# Sheet1.net
KiCad netlist of a schematic drawn in Altium Designer
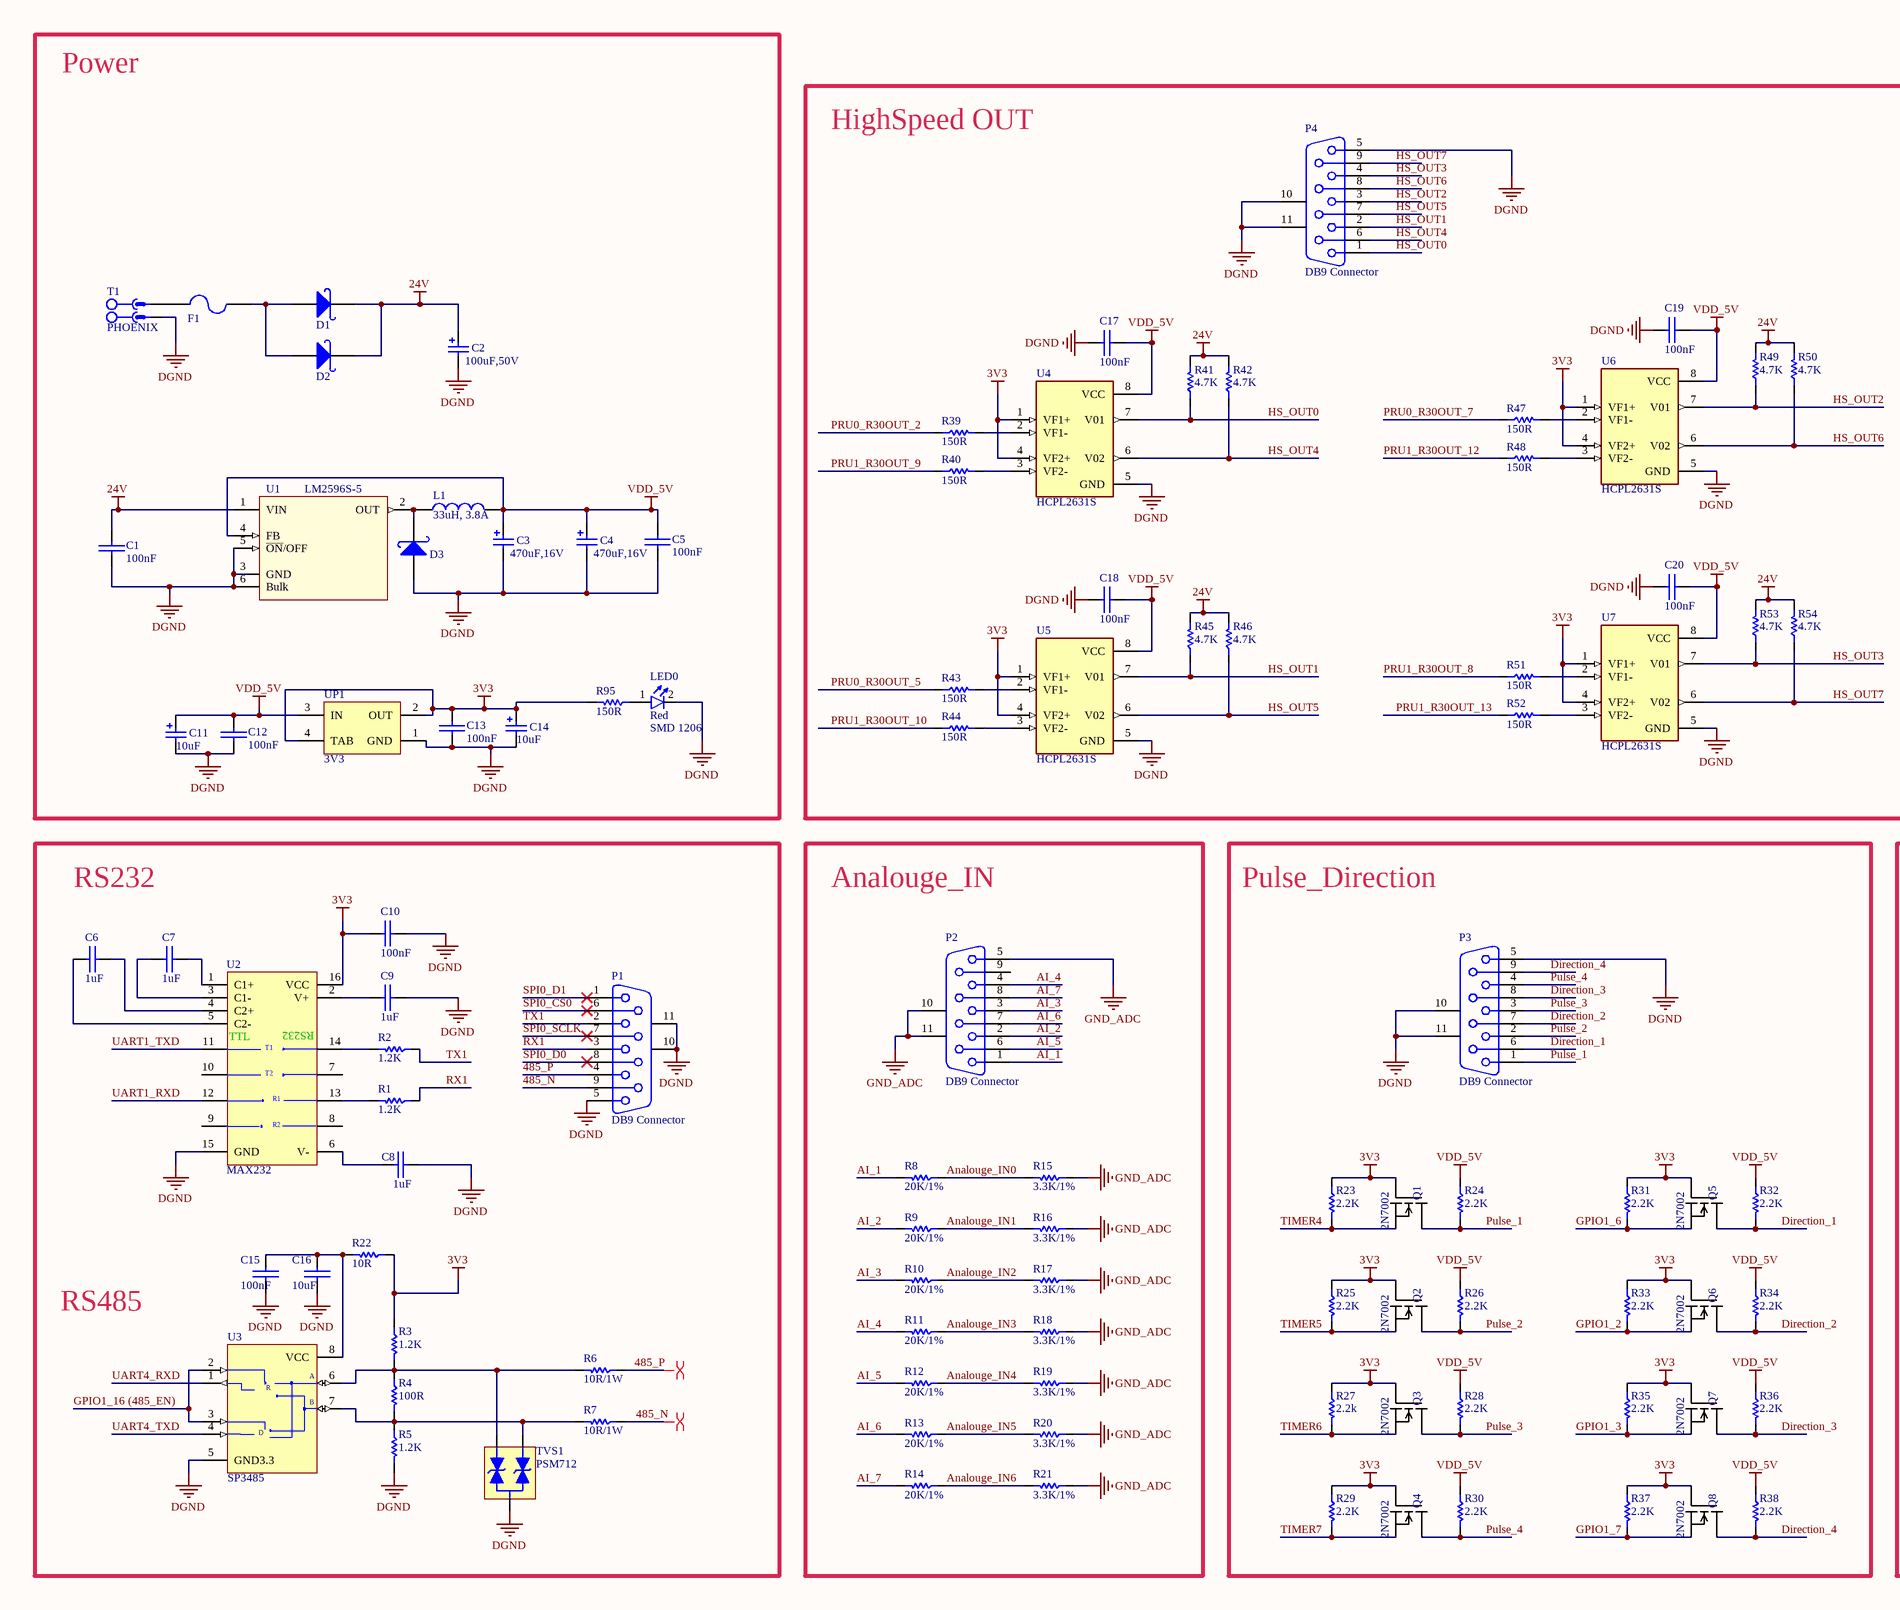
[diagram p0: Sheet1.SchDoc, left]
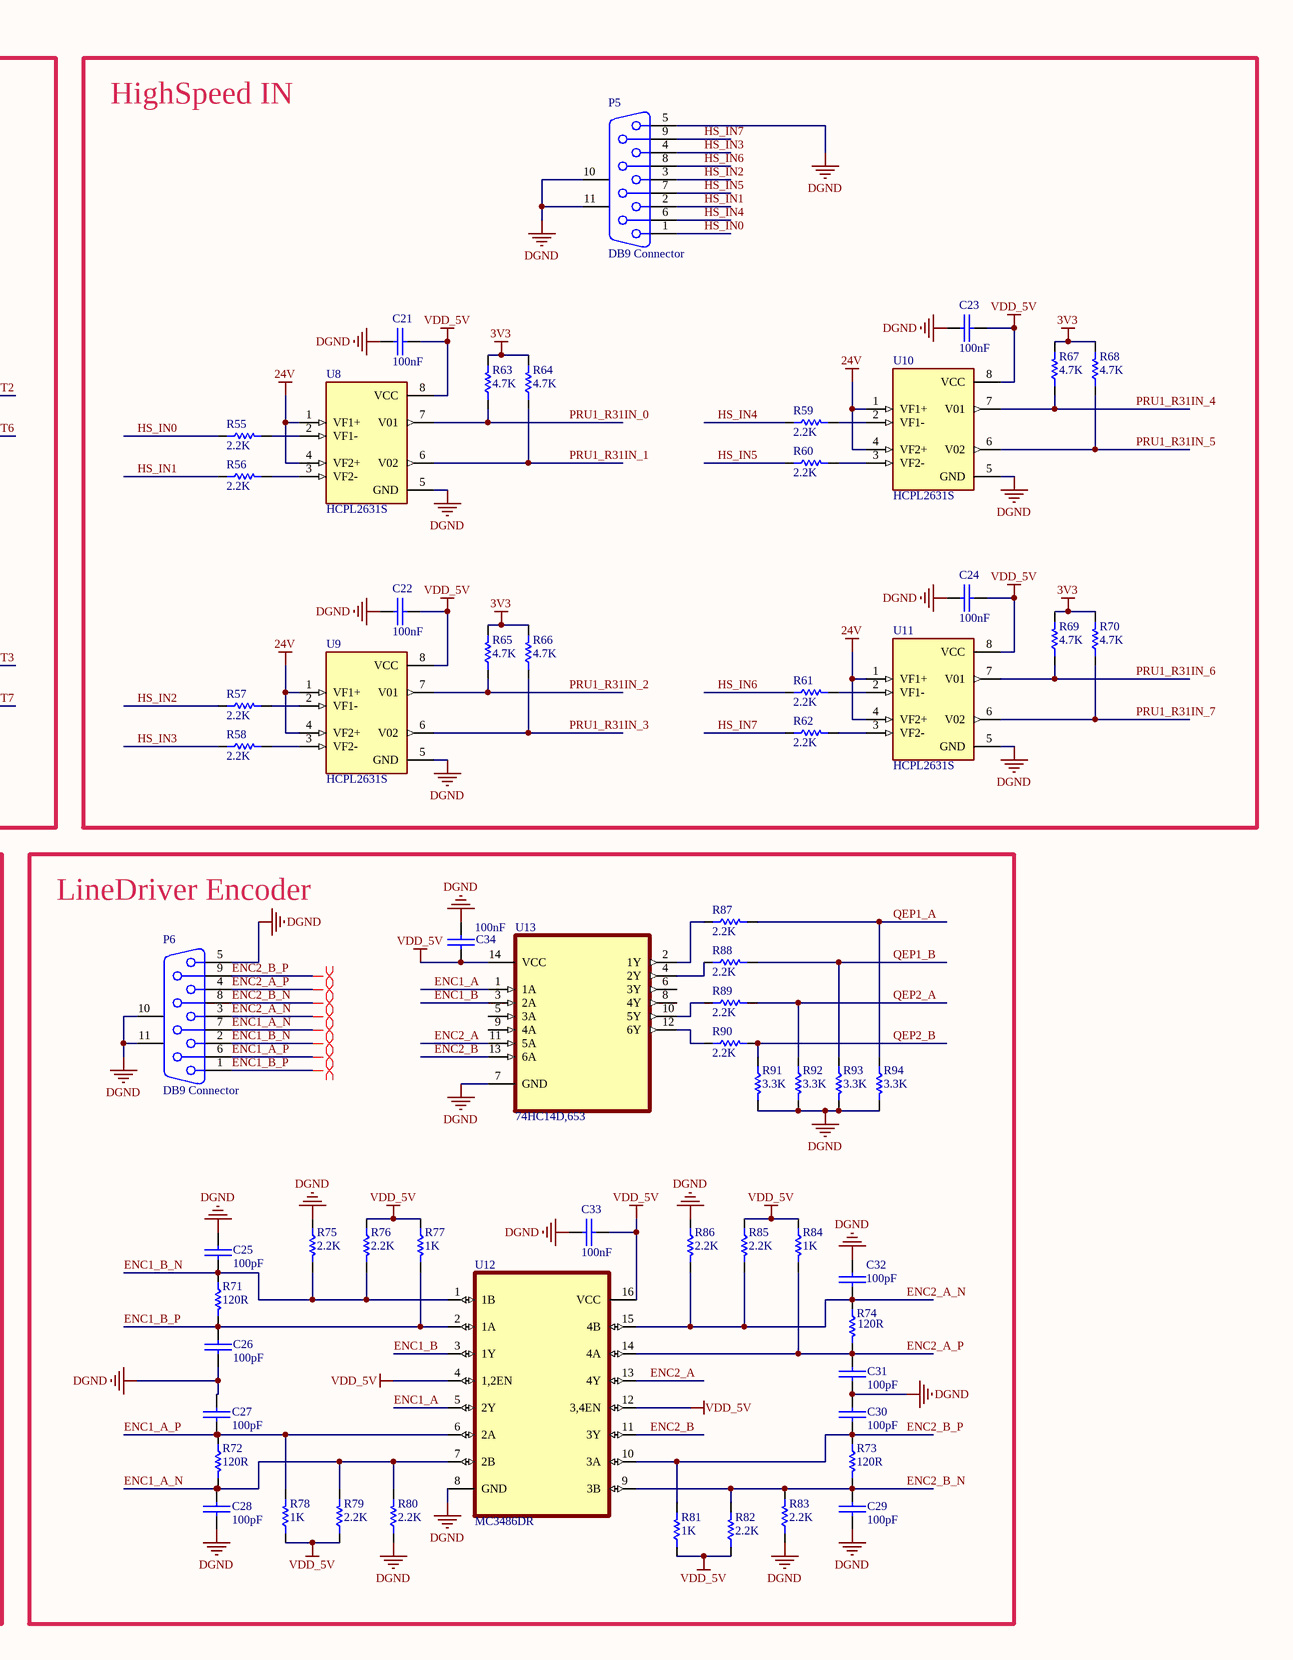
[diagram p1: Sheet1.SchDoc, right]

(export (version "E")
  (design (tool "Eeschema 10.0.6"))
  (components
    (comp (ref "C1")
      (value "100nF")
      (footprint "SMD_CAP_0805")
      (description "Bipolar Capacitor")
      (fields (field (name "VOLTAGE") "100V") (field (name "DESIGNER") "Saeid Jorablo"))
      (libsource (lib "My_Library") (part "Cap-Bipolar"))
    )
    (comp (ref "C2")
      (value "100uF,50V")
      (footprint "WCAP-AS5H_8x10.5")
      (description "WCAP-AS5H SMT Aluminum Electrolytic Capacitors, D8mm x L10.5mm, 47uF, +/-20%, 50VDC")
      (fields (field (name "PART NUMBER") "865230653012") (field (name "PUBLISHER") "Wurth Elektronik"))
      (libsource (lib "Altium_WCAP-AS5H (rev19a)") (part "865230653012"))
    )
    (comp (ref "C3")
      (value "470uF,16V")
      (footprint "WCAP-AS5H_8x10.5")
      (description "WCAP-AS5H SMT Aluminum Electrolytic Capacitors, D8mm x L10.5mm, 47uF, +/-20%, 50VDC")
      (fields (field (name "PART NUMBER") "865230653012") (field (name "PUBLISHER") "Wurth Elektronik"))
      (libsource (lib "Altium_WCAP-AS5H (rev19a)") (part "865230653012"))
    )
    (comp (ref "C4")
      (value "470uF,16V")
      (footprint "WCAP-AS5H_8x10.5")
      (description "WCAP-AS5H SMT Aluminum Electrolytic Capacitors, D8mm x L10.5mm, 47uF, +/-20%, 50VDC")
      (fields (field (name "PART NUMBER") "865230653012") (field (name "PUBLISHER") "Wurth Elektronik"))
      (libsource (lib "Altium_WCAP-AS5H (rev19a)") (part "865230653012"))
    )
    (comp (ref "C5")
      (value "100nF")
      (footprint "SMD_CAP_0805")
      (description "Bipolar Capacitor")
      (fields (field (name "VOLTAGE") "100V") (field (name "DESIGNER") "Saeid Jorablo"))
      (libsource (lib "My_Library") (part "Cap-Bipolar"))
    )
    (comp (ref "C6")
      (value "1uF")
      (footprint "SMD_CAP_0805")
      (description "Bipolar Capacitor")
      (fields (field (name "VOLTAGE") "100V") (field (name "DESIGNER") "Saeid Jorablo"))
      (libsource (lib "My_Library") (part "Cap-Bipolar"))
    )
    (comp (ref "C7")
      (value "1uF")
      (footprint "SMD_CAP_0805")
      (description "Bipolar Capacitor")
      (fields (field (name "VOLTAGE") "100V") (field (name "DESIGNER") "Saeid Jorablo"))
      (libsource (lib "My_Library") (part "Cap-Bipolar"))
    )
    (comp (ref "C8")
      (value "1uF")
      (footprint "SMD_CAP_0805")
      (description "Bipolar Capacitor")
      (fields (field (name "VOLTAGE") "100V") (field (name "DESIGNER") "Saeid Jorablo"))
      (libsource (lib "My_Library") (part "Cap-Bipolar"))
    )
    (comp (ref "C9")
      (value "1uF")
      (footprint "SMD_CAP_0805")
      (description "Bipolar Capacitor")
      (fields (field (name "VOLTAGE") "100V") (field (name "DESIGNER") "Saeid Jorablo"))
      (libsource (lib "My_Library") (part "Cap-Bipolar"))
    )
    (comp (ref "C10")
      (value "100nF")
      (footprint "SMD_CAP_0805")
      (description "Bipolar Capacitor")
      (fields (field (name "VOLTAGE") "100V") (field (name "DESIGNER") "Saeid Jorablo"))
      (libsource (lib "My_Library") (part "Cap-Bipolar"))
    )
    (comp (ref "C11")
      (value "10uF")
      (footprint "WCAP-AS5H_4x5.5")
      (description "WCAP-AS5H SMT Aluminum Electrolytic Capacitors, D4mm x L5.5mm, 22uF, +/-20%, 6.3VDC")
      (fields (field (name "PART NUMBER") "865230140001") (field (name "PUBLISHER") "Wurth Elektronik"))
      (libsource (lib "Altium_WCAP-AS5H (rev19a)") (part "865230140001"))
    )
    (comp (ref "C12")
      (value "100nF")
      (footprint "SMD_CAP_0805")
      (description "Bipolar Capacitor")
      (fields (field (name "VOLTAGE") "100V") (field (name "DESIGNER") "Saeid Jorablo"))
      (libsource (lib "My_Library") (part "Cap-Bipolar"))
    )
    (comp (ref "C13")
      (value "100nF")
      (footprint "SMD_CAP_0805")
      (description "Bipolar Capacitor")
      (fields (field (name "VOLTAGE") "100V") (field (name "DESIGNER") "Saeid Jorablo"))
      (libsource (lib "My_Library") (part "Cap-Bipolar"))
    )
    (comp (ref "C14")
      (value "10uF")
      (footprint "WCAP-AS5H_4x5.5")
      (description "WCAP-AS5H SMT Aluminum Electrolytic Capacitors, D4mm x L5.5mm, 22uF, +/-20%, 6.3VDC")
      (fields (field (name "PART NUMBER") "865230140001") (field (name "PUBLISHER") "Wurth Elektronik"))
      (libsource (lib "Altium_WCAP-AS5H (rev19a)") (part "865230140001"))
    )
    (comp (ref "C15")
      (value "100nF")
      (footprint "SMD_CAP_0805")
      (description "Bipolar Capacitor")
      (fields (field (name "VOLTAGE") "100V") (field (name "DESIGNER") "Saeid Jorablo"))
      (libsource (lib "My_Library") (part "Cap-Bipolar"))
    )
    (comp (ref "C16")
      (value "10uF")
      (footprint "SMD_CAP_0805")
      (description "Bipolar Capacitor")
      (fields (field (name "VOLTAGE") "100V") (field (name "DESIGNER") "Saeid Jorablo"))
      (libsource (lib "My_Library") (part "Cap-Bipolar"))
    )
    (comp (ref "C17")
      (value "100nF")
      (footprint "SMD_CAP_0805")
      (description "Bipolar Capacitor")
      (fields (field (name "VOLTAGE") "100V") (field (name "DESIGNER") "Saeid Jorablo"))
      (libsource (lib "My_Library") (part "Cap-Bipolar"))
    )
    (comp (ref "C18")
      (value "100nF")
      (footprint "SMD_CAP_0805")
      (description "Bipolar Capacitor")
      (fields (field (name "VOLTAGE") "100V") (field (name "DESIGNER") "Saeid Jorablo"))
      (libsource (lib "My_Library") (part "Cap-Bipolar"))
    )
    (comp (ref "C19")
      (value "100nF")
      (footprint "SMD_CAP_0805")
      (description "Bipolar Capacitor")
      (fields (field (name "VOLTAGE") "100V") (field (name "DESIGNER") "Saeid Jorablo"))
      (libsource (lib "My_Library") (part "Cap-Bipolar"))
    )
    (comp (ref "C20")
      (value "100nF")
      (footprint "SMD_CAP_0805")
      (description "Bipolar Capacitor")
      (fields (field (name "VOLTAGE") "100V") (field (name "DESIGNER") "Saeid Jorablo"))
      (libsource (lib "My_Library") (part "Cap-Bipolar"))
    )
    (comp (ref "C21")
      (value "100nF")
      (footprint "SMD_CAP_0805")
      (description "Bipolar Capacitor")
      (fields (field (name "VOLTAGE") "100V") (field (name "DESIGNER") "Saeid Jorablo"))
      (libsource (lib "My_Library") (part "Cap-Bipolar"))
    )
    (comp (ref "C22")
      (value "100nF")
      (footprint "SMD_CAP_0805")
      (description "Bipolar Capacitor")
      (fields (field (name "VOLTAGE") "100V") (field (name "DESIGNER") "Saeid Jorablo"))
      (libsource (lib "My_Library") (part "Cap-Bipolar"))
    )
    (comp (ref "C23")
      (value "100nF")
      (footprint "SMD_CAP_0805")
      (description "Bipolar Capacitor")
      (fields (field (name "VOLTAGE") "100V") (field (name "DESIGNER") "Saeid Jorablo"))
      (libsource (lib "My_Library") (part "Cap-Bipolar"))
    )
    (comp (ref "C24")
      (value "100nF")
      (footprint "SMD_CAP_0805")
      (description "Bipolar Capacitor")
      (fields (field (name "VOLTAGE") "100V") (field (name "DESIGNER") "Saeid Jorablo"))
      (libsource (lib "My_Library") (part "Cap-Bipolar"))
    )
    (comp (ref "C25")
      (value "100pF")
      (footprint "SMD_CAP_0805")
      (description "Bipolar Capacitor")
      (fields (field (name "VOLTAGE") "100V") (field (name "DESIGNER") "Saeid Jorablo"))
      (libsource (lib "My_Library") (part "Cap-Bipolar"))
    )
    (comp (ref "C26")
      (value "100pF")
      (footprint "SMD_CAP_0805")
      (description "Bipolar Capacitor")
      (fields (field (name "VOLTAGE") "100V") (field (name "DESIGNER") "Saeid Jorablo"))
      (libsource (lib "My_Library") (part "Cap-Bipolar"))
    )
    (comp (ref "C27")
      (value "100pF")
      (footprint "SMD_CAP_0805")
      (description "Bipolar Capacitor")
      (fields (field (name "VOLTAGE") "100V") (field (name "DESIGNER") "Saeid Jorablo"))
      (libsource (lib "My_Library") (part "Cap-Bipolar"))
    )
    (comp (ref "C28")
      (value "100pF")
      (footprint "SMD_CAP_0805")
      (description "Bipolar Capacitor")
      (fields (field (name "VOLTAGE") "100V") (field (name "DESIGNER") "Saeid Jorablo"))
      (libsource (lib "My_Library") (part "Cap-Bipolar"))
    )
    (comp (ref "C29")
      (value "100pF")
      (footprint "SMD_CAP_0805")
      (description "Bipolar Capacitor")
      (fields (field (name "VOLTAGE") "100V") (field (name "DESIGNER") "Saeid Jorablo"))
      (libsource (lib "My_Library") (part "Cap-Bipolar"))
    )
    (comp (ref "C30")
      (value "100pF")
      (footprint "SMD_CAP_0805")
      (description "Bipolar Capacitor")
      (fields (field (name "VOLTAGE") "100V") (field (name "DESIGNER") "Saeid Jorablo"))
      (libsource (lib "My_Library") (part "Cap-Bipolar"))
    )
    (comp (ref "C31")
      (value "100pF")
      (footprint "SMD_CAP_0805")
      (description "Bipolar Capacitor")
      (fields (field (name "VOLTAGE") "100V") (field (name "DESIGNER") "Saeid Jorablo"))
      (libsource (lib "My_Library") (part "Cap-Bipolar"))
    )
    (comp (ref "C32")
      (value "100pF")
      (footprint "SMD_CAP_0805")
      (description "Bipolar Capacitor")
      (fields (field (name "VOLTAGE") "100V") (field (name "DESIGNER") "Saeid Jorablo"))
      (libsource (lib "My_Library") (part "Cap-Bipolar"))
    )
    (comp (ref "C33")
      (value "100nF")
      (footprint "SMD_CAP_0805")
      (description "Bipolar Capacitor")
      (fields (field (name "VOLTAGE") "100V") (field (name "DESIGNER") "Saeid Jorablo"))
      (libsource (lib "My_Library") (part "Cap-Bipolar"))
    )
    (comp (ref "C34")
      (value "100nF")
      (footprint "SMD_CAP_0805")
      (description "Bipolar Capacitor")
      (fields (field (name "VOLTAGE") "100V") (field (name "DESIGNER") "Saeid Jorablo"))
      (libsource (lib "My_Library") (part "Cap-Bipolar"))
    )
    (comp (ref "D1")
      (value "1n5822")
      (footprint "Diode 1N4007 SMD")
      (description "Schottky Rectifiers")
      (fields
        (field (name "MANUFACTURER") "ON Semiconductor/Fairchild")
        (field (name "DESIGNER") "Abbas Basereh")
      )
      (libsource (lib "Altium") (part "1N5822 SMD"))
    )
    (comp (ref "D2")
      (value "1n5822")
      (footprint "Diode 1N4007 SMD")
      (description "Schottky Rectifiers")
      (fields
        (field (name "MANUFACTURER") "ON Semiconductor/Fairchild")
        (field (name "DESIGNER") "Abbas Basereh")
      )
      (libsource (lib "Altium") (part "1N5822 SMD"))
    )
    (comp (ref "D3")
      (value "1n5822")
      (footprint "Diode 1N4007 SMD")
      (description "Schottky Rectifiers")
      (fields
        (field (name "MANUFACTURER") "ON Semiconductor/Fairchild")
        (field (name "DESIGNER") "Abbas Basereh")
      )
      (libsource (lib "Altium") (part "1N5822 SMD"))
    )
    (comp (ref "F1")
      (value "F=1.0 A")
      (footprint "1206 FUSE")
      (description "SMD Fuses 1206")
      (fields (field (name "DESIGNER") "Abbas Basereh"))
      (libsource (lib "Altium") (part "Fuse SMD1206"))
    )
    (comp (ref "L1")
      (value "33uH, 3.8A")
      (footprint "WE-PD_1210")
      (description "WE-PD SMT Power Inductor, size 1210, 47uH, 3.8A")
      (fields (field (name "PART NUMBER") "7447709470") (field (name "PUBLISHER") "Wurth Elektronik"))
      (libsource (lib "ALTIUM-WE-PD-rev19b") (part "7447709470"))
    )
    (comp (ref "LED0")
      (value "Red")
      (footprint "LED-3mm")
      (description "LED")
      (fields
        (field (name "COLOR") "Red")
        (field (name "SIZE") "SMD 1206")
        (field (name "DESIGNER") "Saeid Jorablo")
      )
      (libsource (lib "My_Library") (part "LED"))
    )
    (comp (ref "P1")
      (value "DB9 Connector")
      (footprint "DB9 Female")
      (description "Receptacle Assembly, 9 Position, Right Angle")
      (fields (field (name "PUBLISHER") "Altium Limited"))
      (libsource (lib "My_Library") (part "DB9 Connector"))
    )
    (comp (ref "P2")
      (value "DB9 Connector")
      (footprint "DB9 Female")
      (description "Receptacle Assembly, 9 Position, Right Angle")
      (fields (field (name "PUBLISHER") "Altium Limited"))
      (libsource (lib "My_Library") (part "DB9 Connector"))
    )
    (comp (ref "P3")
      (value "DB9 Connector")
      (footprint "DB9 Female")
      (description "Receptacle Assembly, 9 Position, Right Angle")
      (fields (field (name "PUBLISHER") "Altium Limited"))
      (libsource (lib "My_Library") (part "DB9 Connector"))
    )
    (comp (ref "P4")
      (value "DB9 Connector")
      (footprint "DB9 Female")
      (description "Receptacle Assembly, 9 Position, Right Angle")
      (fields (field (name "PUBLISHER") "Altium Limited"))
      (libsource (lib "My_Library") (part "DB9 Connector"))
    )
    (comp (ref "P5")
      (value "DB9 Connector")
      (footprint "DB9 Female")
      (description "Receptacle Assembly, 9 Position, Right Angle")
      (fields (field (name "PUBLISHER") "Altium Limited"))
      (libsource (lib "My_Library") (part "DB9 Connector"))
    )
    (comp (ref "P6")
      (value "DB9 Connector")
      (footprint "DB9 Female")
      (description "Receptacle Assembly, 9 Position, Right Angle")
      (fields (field (name "PUBLISHER") "Altium Limited"))
      (libsource (lib "My_Library") (part "DB9 Connector"))
    )
    (comp (ref "Q1")
      (value "2N7002")
      (footprint "*SOT23")
      (description "Transistor NPN Mos 2N7002 SILICONIX miliampere=100 V=60 SOt23")
      (fields (field (name "MF") "STMicroelectronics"))
      (libsource (lib "2N7002") (part "2N7002"))
    )
    (comp (ref "Q2")
      (value "2N7002")
      (footprint "*SOT23")
      (description "Transistor NPN Mos 2N7002 SILICONIX miliampere=100 V=60 SOt23")
      (fields (field (name "MF") "STMicroelectronics"))
      (libsource (lib "2N7002") (part "2N7002"))
    )
    (comp (ref "Q3")
      (value "2N7002")
      (footprint "*SOT23")
      (description "Transistor NPN Mos 2N7002 SILICONIX miliampere=100 V=60 SOt23")
      (fields (field (name "MF") "STMicroelectronics"))
      (libsource (lib "2N7002") (part "2N7002"))
    )
    (comp (ref "Q4")
      (value "2N7002")
      (footprint "*SOT23")
      (description "Transistor NPN Mos 2N7002 SILICONIX miliampere=100 V=60 SOt23")
      (fields (field (name "MF") "STMicroelectronics"))
      (libsource (lib "2N7002") (part "2N7002"))
    )
    (comp (ref "Q5")
      (value "2N7002")
      (footprint "*SOT23")
      (description "Transistor NPN Mos 2N7002 SILICONIX miliampere=100 V=60 SOt23")
      (fields (field (name "MF") "STMicroelectronics"))
      (libsource (lib "2N7002") (part "2N7002"))
    )
    (comp (ref "Q6")
      (value "2N7002")
      (footprint "*SOT23")
      (description "Transistor NPN Mos 2N7002 SILICONIX miliampere=100 V=60 SOt23")
      (fields (field (name "MF") "STMicroelectronics"))
      (libsource (lib "2N7002") (part "2N7002"))
    )
    (comp (ref "Q7")
      (value "2N7002")
      (footprint "*SOT23")
      (description "Transistor NPN Mos 2N7002 SILICONIX miliampere=100 V=60 SOt23")
      (fields (field (name "MF") "STMicroelectronics"))
      (libsource (lib "2N7002") (part "2N7002"))
    )
    (comp (ref "Q8")
      (value "2N7002")
      (footprint "*SOT23")
      (description "Transistor NPN Mos 2N7002 SILICONIX miliampere=100 V=60 SOt23")
      (fields (field (name "MF") "STMicroelectronics"))
      (libsource (lib "2N7002") (part "2N7002"))
    )
    (comp (ref "R1")
      (value "1.2K")
      (footprint "RES 0805 (2012X06L)")
      (description "Resistor")
      (fields (field (name "TOLERANCE") "5%") (field (name "POWER") "1/8 W"))
      (libsource (lib "My_Library") (part "Resistor"))
    )
    (comp (ref "R2")
      (value "1.2K")
      (footprint "RES 0805 (2012X06L)")
      (description "Resistor")
      (fields (field (name "TOLERANCE") "5%") (field (name "POWER") "1/8 W"))
      (libsource (lib "My_Library") (part "Resistor"))
    )
    (comp (ref "R3")
      (value "1.2K")
      (footprint "RES 0805 (2012X06L)")
      (description "Resistor")
      (fields (field (name "TOLERANCE") "5%") (field (name "POWER") "1/8 W"))
      (libsource (lib "My_Library") (part "Resistor"))
    )
    (comp (ref "R4")
      (value "100R")
      (footprint "RES 1206 (3216X08L)")
      (description "Resistor")
      (fields (field (name "TOLERANCE") "5%") (field (name "POWER") "1/8 W"))
      (libsource (lib "My_Library") (part "Resistor"))
    )
    (comp (ref "R5")
      (value "1.2K")
      (footprint "RES 0805 (2012X06L)")
      (description "Resistor")
      (fields (field (name "TOLERANCE") "5%") (field (name "POWER") "1/8 W"))
      (libsource (lib "My_Library") (part "Resistor"))
    )
    (comp (ref "R6")
      (value "10R/1W")
      (footprint "RES 1206 (3216X08L)")
      (description "Resistor")
      (fields (field (name "TOLERANCE") "5%") (field (name "POWER") "1/8 W"))
      (libsource (lib "My_Library") (part "Resistor"))
    )
    (comp (ref "R7")
      (value "10R/1W")
      (footprint "RES 1206 (3216X08L)")
      (description "Resistor")
      (fields (field (name "TOLERANCE") "5%") (field (name "POWER") "1/8 W"))
      (libsource (lib "My_Library") (part "Resistor"))
    )
    (comp (ref "R8")
      (value "20K/1%")
      (footprint "RES 0805 (2012X06L)")
      (description "Resistor")
      (fields (field (name "TOLERANCE") "5%") (field (name "POWER") "1/8 W"))
      (libsource (lib "My_Library") (part "Resistor"))
    )
    (comp (ref "R9")
      (value "20K/1%")
      (footprint "RES 0805 (2012X06L)")
      (description "Resistor")
      (fields (field (name "TOLERANCE") "5%") (field (name "POWER") "1/8 W"))
      (libsource (lib "My_Library") (part "Resistor"))
    )
    (comp (ref "R10")
      (value "20K/1%")
      (footprint "RES 0805 (2012X06L)")
      (description "Resistor")
      (fields (field (name "TOLERANCE") "5%") (field (name "POWER") "1/8 W"))
      (libsource (lib "My_Library") (part "Resistor"))
    )
    (comp (ref "R11")
      (value "20K/1%")
      (footprint "RES 0805 (2012X06L)")
      (description "Resistor")
      (fields (field (name "TOLERANCE") "5%") (field (name "POWER") "1/8 W"))
      (libsource (lib "My_Library") (part "Resistor"))
    )
    (comp (ref "R12")
      (value "20K/1%")
      (footprint "RES 0805 (2012X06L)")
      (description "Resistor")
      (fields (field (name "TOLERANCE") "5%") (field (name "POWER") "1/8 W"))
      (libsource (lib "My_Library") (part "Resistor"))
    )
    (comp (ref "R13")
      (value "20K/1%")
      (footprint "RES 0805 (2012X06L)")
      (description "Resistor")
      (fields (field (name "TOLERANCE") "5%") (field (name "POWER") "1/8 W"))
      (libsource (lib "My_Library") (part "Resistor"))
    )
    (comp (ref "R14")
      (value "20K/1%")
      (footprint "RES 0805 (2012X06L)")
      (description "Resistor")
      (fields (field (name "TOLERANCE") "5%") (field (name "POWER") "1/8 W"))
      (libsource (lib "My_Library") (part "Resistor"))
    )
    (comp (ref "R15")
      (value "3.3K/1%")
      (footprint "RES 0805 (2012X06L)")
      (description "Resistor")
      (fields (field (name "TOLERANCE") "5%") (field (name "POWER") "1/8 W"))
      (libsource (lib "My_Library") (part "Resistor"))
    )
    (comp (ref "R16")
      (value "3.3K/1%")
      (footprint "RES 0805 (2012X06L)")
      (description "Resistor")
      (fields (field (name "TOLERANCE") "5%") (field (name "POWER") "1/8 W"))
      (libsource (lib "My_Library") (part "Resistor"))
    )
    (comp (ref "R17")
      (value "3.3K/1%")
      (footprint "RES 0805 (2012X06L)")
      (description "Resistor")
      (fields (field (name "TOLERANCE") "5%") (field (name "POWER") "1/8 W"))
      (libsource (lib "My_Library") (part "Resistor"))
    )
    (comp (ref "R18")
      (value "3.3K/1%")
      (footprint "RES 0805 (2012X06L)")
      (description "Resistor")
      (fields (field (name "TOLERANCE") "5%") (field (name "POWER") "1/8 W"))
      (libsource (lib "My_Library") (part "Resistor"))
    )
    (comp (ref "R19")
      (value "3.3K/1%")
      (footprint "RES 0805 (2012X06L)")
      (description "Resistor")
      (fields (field (name "TOLERANCE") "5%") (field (name "POWER") "1/8 W"))
      (libsource (lib "My_Library") (part "Resistor"))
    )
    (comp (ref "R20")
      (value "3.3K/1%")
      (footprint "RES 0805 (2012X06L)")
      (description "Resistor")
      (fields (field (name "TOLERANCE") "5%") (field (name "POWER") "1/8 W"))
      (libsource (lib "My_Library") (part "Resistor"))
    )
    (comp (ref "R21")
      (value "3.3K/1%")
      (footprint "RES 0805 (2012X06L)")
      (description "Resistor")
      (fields (field (name "TOLERANCE") "5%") (field (name "POWER") "1/8 W"))
      (libsource (lib "My_Library") (part "Resistor"))
    )
    (comp (ref "R22")
      (value "10R")
      (footprint "RES 0805 (2012X06L)")
      (description "Resistor")
      (fields (field (name "TOLERANCE") "5%") (field (name "POWER") "1/8 W"))
      (libsource (lib "My_Library") (part "Resistor"))
    )
    (comp (ref "R23")
      (value "2.2K")
      (footprint "RES 0805 (2012X06L)")
      (description "Resistor")
      (fields (field (name "TOLERANCE") "5%") (field (name "POWER") "1/8 W"))
      (libsource (lib "My_Library") (part "Resistor"))
    )
    (comp (ref "R24")
      (value "2.2K")
      (footprint "RES 0805 (2012X06L)")
      (description "Resistor")
      (fields (field (name "TOLERANCE") "5%") (field (name "POWER") "1/8 W"))
      (libsource (lib "My_Library") (part "Resistor"))
    )
    (comp (ref "R25")
      (value "2.2K")
      (footprint "RES 0805 (2012X06L)")
      (description "Resistor")
      (fields (field (name "TOLERANCE") "5%") (field (name "POWER") "1/8 W"))
      (libsource (lib "My_Library") (part "Resistor"))
    )
    (comp (ref "R26")
      (value "2.2K")
      (footprint "RES 0805 (2012X06L)")
      (description "Resistor")
      (fields (field (name "TOLERANCE") "5%") (field (name "POWER") "1/8 W"))
      (libsource (lib "My_Library") (part "Resistor"))
    )
    (comp (ref "R27")
      (value "2.2k")
      (footprint "RES 0805 (2012X06L)")
      (description "Resistor")
      (fields (field (name "TOLERANCE") "5%") (field (name "POWER") "1/8 W"))
      (libsource (lib "My_Library") (part "Resistor"))
    )
    (comp (ref "R28")
      (value "2.2K")
      (footprint "RES 0805 (2012X06L)")
      (description "Resistor")
      (fields (field (name "TOLERANCE") "5%") (field (name "POWER") "1/8 W"))
      (libsource (lib "My_Library") (part "Resistor"))
    )
    (comp (ref "R29")
      (value "2.2K")
      (footprint "RES 0805 (2012X06L)")
      (description "Resistor")
      (fields (field (name "TOLERANCE") "5%") (field (name "POWER") "1/8 W"))
      (libsource (lib "My_Library") (part "Resistor"))
    )
    (comp (ref "R30")
      (value "2.2K")
      (footprint "RES 0805 (2012X06L)")
      (description "Resistor")
      (fields (field (name "TOLERANCE") "5%") (field (name "POWER") "1/8 W"))
      (libsource (lib "My_Library") (part "Resistor"))
    )
    (comp (ref "R31")
      (value "2.2K")
      (footprint "RES 0805 (2012X06L)")
      (description "Resistor")
      (fields (field (name "TOLERANCE") "5%") (field (name "POWER") "1/8 W"))
      (libsource (lib "My_Library") (part "Resistor"))
    )
    (comp (ref "R32")
      (value "2.2K")
      (footprint "RES 0805 (2012X06L)")
      (description "Resistor")
      (fields (field (name "TOLERANCE") "5%") (field (name "POWER") "1/8 W"))
      (libsource (lib "My_Library") (part "Resistor"))
    )
    (comp (ref "R33")
      (value "2.2K")
      (footprint "RES 0805 (2012X06L)")
      (description "Resistor")
      (fields (field (name "TOLERANCE") "5%") (field (name "POWER") "1/8 W"))
      (libsource (lib "My_Library") (part "Resistor"))
    )
    (comp (ref "R34")
      (value "2.2K")
      (footprint "RES 0805 (2012X06L)")
      (description "Resistor")
      (fields (field (name "TOLERANCE") "5%") (field (name "POWER") "1/8 W"))
      (libsource (lib "My_Library") (part "Resistor"))
    )
    (comp (ref "R35")
      (value "2.2K")
      (footprint "RES 0805 (2012X06L)")
      (description "Resistor")
      (fields (field (name "TOLERANCE") "5%") (field (name "POWER") "1/8 W"))
      (libsource (lib "My_Library") (part "Resistor"))
    )
    (comp (ref "R36")
      (value "2.2K")
      (footprint "RES 0805 (2012X06L)")
      (description "Resistor")
      (fields (field (name "TOLERANCE") "5%") (field (name "POWER") "1/8 W"))
      (libsource (lib "My_Library") (part "Resistor"))
    )
    (comp (ref "R37")
      (value "2.2K")
      (footprint "RES 0805 (2012X06L)")
      (description "Resistor")
      (fields (field (name "TOLERANCE") "5%") (field (name "POWER") "1/8 W"))
      (libsource (lib "My_Library") (part "Resistor"))
    )
    (comp (ref "R38")
      (value "2.2K")
      (footprint "RES 0805 (2012X06L)")
      (description "Resistor")
      (fields (field (name "TOLERANCE") "5%") (field (name "POWER") "1/8 W"))
      (libsource (lib "My_Library") (part "Resistor"))
    )
    (comp (ref "R39")
      (value "150R")
      (footprint "RES 0805 (2012X06L)")
      (description "Resistor")
      (fields (field (name "TOLERANCE") "5%") (field (name "POWER") "1/8 W"))
      (libsource (lib "My_Library") (part "Resistor"))
    )
    (comp (ref "R40")
      (value "150R")
      (footprint "RES 0805 (2012X06L)")
      (description "Resistor")
      (fields (field (name "TOLERANCE") "5%") (field (name "POWER") "1/8 W"))
      (libsource (lib "My_Library") (part "Resistor"))
    )
    (comp (ref "R41")
      (value "4.7K")
      (footprint "RES 0805 (2012X06L)")
      (description "Resistor")
      (fields (field (name "TOLERANCE") "5%") (field (name "POWER") "1/8 W"))
      (libsource (lib "My_Library") (part "Resistor"))
    )
    (comp (ref "R42")
      (value "4.7K")
      (footprint "RES 0805 (2012X06L)")
      (description "Resistor")
      (fields (field (name "TOLERANCE") "5%") (field (name "POWER") "1/8 W"))
      (libsource (lib "My_Library") (part "Resistor"))
    )
    (comp (ref "R43")
      (value "150R")
      (footprint "RES 0805 (2012X06L)")
      (description "Resistor")
      (fields (field (name "TOLERANCE") "5%") (field (name "POWER") "1/8 W"))
      (libsource (lib "My_Library") (part "Resistor"))
    )
    (comp (ref "R44")
      (value "150R")
      (footprint "RES 0805 (2012X06L)")
      (description "Resistor")
      (fields (field (name "TOLERANCE") "5%") (field (name "POWER") "1/8 W"))
      (libsource (lib "My_Library") (part "Resistor"))
    )
    (comp (ref "R45")
      (value "4.7K")
      (footprint "RES 0805 (2012X06L)")
      (description "Resistor")
      (fields (field (name "TOLERANCE") "5%") (field (name "POWER") "1/8 W"))
      (libsource (lib "My_Library") (part "Resistor"))
    )
    (comp (ref "R46")
      (value "4.7K")
      (footprint "RES 0805 (2012X06L)")
      (description "Resistor")
      (fields (field (name "TOLERANCE") "5%") (field (name "POWER") "1/8 W"))
      (libsource (lib "My_Library") (part "Resistor"))
    )
    (comp (ref "R47")
      (value "150R")
      (footprint "RES 0805 (2012X06L)")
      (description "Resistor")
      (fields (field (name "TOLERANCE") "5%") (field (name "POWER") "1/8 W"))
      (libsource (lib "My_Library") (part "Resistor"))
    )
    (comp (ref "R48")
      (value "150R")
      (footprint "RES 0805 (2012X06L)")
      (description "Resistor")
      (fields (field (name "TOLERANCE") "5%") (field (name "POWER") "1/8 W"))
      (libsource (lib "My_Library") (part "Resistor"))
    )
    (comp (ref "R49")
      (value "4.7K")
      (footprint "RES 0805 (2012X06L)")
      (description "Resistor")
      (fields (field (name "TOLERANCE") "5%") (field (name "POWER") "1/8 W"))
      (libsource (lib "My_Library") (part "Resistor"))
    )
    (comp (ref "R50")
      (value "4.7K")
      (footprint "RES 0805 (2012X06L)")
      (description "Resistor")
      (fields (field (name "TOLERANCE") "5%") (field (name "POWER") "1/8 W"))
      (libsource (lib "My_Library") (part "Resistor"))
    )
    (comp (ref "R51")
      (value "150R")
      (footprint "RES 0805 (2012X06L)")
      (description "Resistor")
      (fields (field (name "TOLERANCE") "5%") (field (name "POWER") "1/8 W"))
      (libsource (lib "My_Library") (part "Resistor"))
    )
    (comp (ref "R52")
      (value "150R")
      (footprint "RES 0805 (2012X06L)")
      (description "Resistor")
      (fields (field (name "TOLERANCE") "5%") (field (name "POWER") "1/8 W"))
      (libsource (lib "My_Library") (part "Resistor"))
    )
    (comp (ref "R53")
      (value "4.7K")
      (footprint "RES 0805 (2012X06L)")
      (description "Resistor")
      (fields (field (name "TOLERANCE") "5%") (field (name "POWER") "1/8 W"))
      (libsource (lib "My_Library") (part "Resistor"))
    )
    (comp (ref "R54")
      (value "4.7K")
      (footprint "RES 0805 (2012X06L)")
      (description "Resistor")
      (fields (field (name "TOLERANCE") "5%") (field (name "POWER") "1/8 W"))
      (libsource (lib "My_Library") (part "Resistor"))
    )
    (comp (ref "R55")
      (value "2.2K")
      (footprint "RES 0805 (2012X06L)")
      (description "Resistor")
      (fields (field (name "TOLERANCE") "5%") (field (name "POWER") "1/8 W"))
      (libsource (lib "My_Library") (part "Resistor"))
    )
    (comp (ref "R56")
      (value "2.2K")
      (footprint "RES 0805 (2012X06L)")
      (description "Resistor")
      (fields (field (name "TOLERANCE") "5%") (field (name "POWER") "1/8 W"))
      (libsource (lib "My_Library") (part "Resistor"))
    )
    (comp (ref "R57")
      (value "2.2K")
      (footprint "RES 0805 (2012X06L)")
      (description "Resistor")
      (fields (field (name "TOLERANCE") "5%") (field (name "POWER") "1/8 W"))
      (libsource (lib "My_Library") (part "Resistor"))
    )
    (comp (ref "R58")
      (value "2.2K")
      (footprint "RES 0805 (2012X06L)")
      (description "Resistor")
      (fields (field (name "TOLERANCE") "5%") (field (name "POWER") "1/8 W"))
      (libsource (lib "My_Library") (part "Resistor"))
    )
    (comp (ref "R59")
      (value "2.2K")
      (footprint "RES 0805 (2012X06L)")
      (description "Resistor")
      (fields (field (name "TOLERANCE") "5%") (field (name "POWER") "1/8 W"))
      (libsource (lib "My_Library") (part "Resistor"))
    )
    (comp (ref "R60")
      (value "2.2K")
      (footprint "RES 0805 (2012X06L)")
      (description "Resistor")
      (fields (field (name "TOLERANCE") "5%") (field (name "POWER") "1/8 W"))
      (libsource (lib "My_Library") (part "Resistor"))
    )
    (comp (ref "R61")
      (value "2.2K")
      (footprint "RES 0805 (2012X06L)")
      (description "Resistor")
      (fields (field (name "TOLERANCE") "5%") (field (name "POWER") "1/8 W"))
      (libsource (lib "My_Library") (part "Resistor"))
    )
    (comp (ref "R62")
      (value "2.2K")
      (footprint "RES 0805 (2012X06L)")
      (description "Resistor")
      (fields (field (name "TOLERANCE") "5%") (field (name "POWER") "1/8 W"))
      (libsource (lib "My_Library") (part "Resistor"))
    )
    (comp (ref "R63")
      (value "4.7K")
      (footprint "RES 0805 (2012X06L)")
      (description "Resistor")
      (fields (field (name "TOLERANCE") "5%") (field (name "POWER") "1/8 W"))
      (libsource (lib "My_Library") (part "Resistor"))
    )
    (comp (ref "R64")
      (value "4.7K")
      (footprint "RES 0805 (2012X06L)")
      (description "Resistor")
      (fields (field (name "TOLERANCE") "5%") (field (name "POWER") "1/8 W"))
      (libsource (lib "My_Library") (part "Resistor"))
    )
    (comp (ref "R65")
      (value "4.7K")
      (footprint "RES 0805 (2012X06L)")
      (description "Resistor")
      (fields (field (name "TOLERANCE") "5%") (field (name "POWER") "1/8 W"))
      (libsource (lib "My_Library") (part "Resistor"))
    )
    (comp (ref "R66")
      (value "4.7K")
      (footprint "RES 0805 (2012X06L)")
      (description "Resistor")
      (fields (field (name "TOLERANCE") "5%") (field (name "POWER") "1/8 W"))
      (libsource (lib "My_Library") (part "Resistor"))
    )
    (comp (ref "R67")
      (value "4.7K")
      (footprint "RES 0805 (2012X06L)")
      (description "Resistor")
      (fields (field (name "TOLERANCE") "5%") (field (name "POWER") "1/8 W"))
      (libsource (lib "My_Library") (part "Resistor"))
    )
    (comp (ref "R68")
      (value "4.7K")
      (footprint "RES 0805 (2012X06L)")
      (description "Resistor")
      (fields (field (name "TOLERANCE") "5%") (field (name "POWER") "1/8 W"))
      (libsource (lib "My_Library") (part "Resistor"))
    )
    (comp (ref "R69")
      (value "4.7K")
      (footprint "RES 0805 (2012X06L)")
      (description "Resistor")
      (fields (field (name "TOLERANCE") "5%") (field (name "POWER") "1/8 W"))
      (libsource (lib "My_Library") (part "Resistor"))
    )
    (comp (ref "R70")
      (value "4.7K")
      (footprint "RES 0805 (2012X06L)")
      (description "Resistor")
      (fields (field (name "TOLERANCE") "5%") (field (name "POWER") "1/8 W"))
      (libsource (lib "My_Library") (part "Resistor"))
    )
    (comp (ref "R71")
      (value "120R")
      (footprint "RES 0805 (2012X06L)")
      (description "Resistor")
      (fields (field (name "TOLERANCE") "5%") (field (name "POWER") "1/8 W"))
      (libsource (lib "My_Library") (part "Resistor"))
    )
    (comp (ref "R72")
      (value "120R")
      (footprint "RES 0805 (2012X06L)")
      (description "Resistor")
      (fields (field (name "TOLERANCE") "5%") (field (name "POWER") "1/8 W"))
      (libsource (lib "My_Library") (part "Resistor"))
    )
    (comp (ref "R73")
      (value "120R")
      (footprint "RES 0805 (2012X06L)")
      (description "Resistor")
      (fields (field (name "TOLERANCE") "5%") (field (name "POWER") "1/8 W"))
      (libsource (lib "My_Library") (part "Resistor"))
    )
    (comp (ref "R74")
      (value "120R")
      (footprint "RES 0805 (2012X06L)")
      (description "Resistor")
      (fields (field (name "TOLERANCE") "5%") (field (name "POWER") "1/8 W"))
      (libsource (lib "My_Library") (part "Resistor"))
    )
    (comp (ref "R75")
      (value "2.2K")
      (footprint "RES 0805 (2012X06L)")
      (description "Resistor")
      (fields (field (name "TOLERANCE") "5%") (field (name "POWER") "1/8 W"))
      (libsource (lib "My_Library") (part "Resistor"))
    )
    (comp (ref "R76")
      (value "2.2K")
      (footprint "RES 0805 (2012X06L)")
      (description "Resistor")
      (fields (field (name "TOLERANCE") "5%") (field (name "POWER") "1/8 W"))
      (libsource (lib "My_Library") (part "Resistor"))
    )
    (comp (ref "R77")
      (value "1K")
      (footprint "RES 0805 (2012X06L)")
      (description "Resistor")
      (fields (field (name "TOLERANCE") "5%") (field (name "POWER") "1/8 W"))
      (libsource (lib "My_Library") (part "Resistor"))
    )
    (comp (ref "R78")
      (value "1K")
      (footprint "RES 0805 (2012X06L)")
      (description "Resistor")
      (fields (field (name "TOLERANCE") "5%") (field (name "POWER") "1/8 W"))
      (libsource (lib "My_Library") (part "Resistor"))
    )
    (comp (ref "R79")
      (value "2.2K")
      (footprint "RES 0805 (2012X06L)")
      (description "Resistor")
      (fields (field (name "TOLERANCE") "5%") (field (name "POWER") "1/8 W"))
      (libsource (lib "My_Library") (part "Resistor"))
    )
    (comp (ref "R80")
      (value "2.2K")
      (footprint "RES 0805 (2012X06L)")
      (description "Resistor")
      (fields (field (name "TOLERANCE") "5%") (field (name "POWER") "1/8 W"))
      (libsource (lib "My_Library") (part "Resistor"))
    )
    (comp (ref "R81")
      (value "1K")
      (footprint "RES 0805 (2012X06L)")
      (description "Resistor")
      (fields (field (name "TOLERANCE") "5%") (field (name "POWER") "1/8 W"))
      (libsource (lib "My_Library") (part "Resistor"))
    )
    (comp (ref "R82")
      (value "2.2K")
      (footprint "RES 0805 (2012X06L)")
      (description "Resistor")
      (fields (field (name "TOLERANCE") "5%") (field (name "POWER") "1/8 W"))
      (libsource (lib "My_Library") (part "Resistor"))
    )
    (comp (ref "R83")
      (value "2.2K")
      (footprint "RES 0805 (2012X06L)")
      (description "Resistor")
      (fields (field (name "TOLERANCE") "5%") (field (name "POWER") "1/8 W"))
      (libsource (lib "My_Library") (part "Resistor"))
    )
    (comp (ref "R84")
      (value "1K")
      (footprint "RES 0805 (2012X06L)")
      (description "Resistor")
      (fields (field (name "TOLERANCE") "5%") (field (name "POWER") "1/8 W"))
      (libsource (lib "My_Library") (part "Resistor"))
    )
    (comp (ref "R85")
      (value "2.2K")
      (footprint "RES 0805 (2012X06L)")
      (description "Resistor")
      (fields (field (name "TOLERANCE") "5%") (field (name "POWER") "1/8 W"))
      (libsource (lib "My_Library") (part "Resistor"))
    )
    (comp (ref "R86")
      (value "2.2K")
      (footprint "RES 0805 (2012X06L)")
      (description "Resistor")
      (fields (field (name "TOLERANCE") "5%") (field (name "POWER") "1/8 W"))
      (libsource (lib "My_Library") (part "Resistor"))
    )
    (comp (ref "R87")
      (value "2.2K")
      (footprint "RES 0805 (2012X06L)")
      (description "Resistor")
      (fields (field (name "TOLERANCE") "5%") (field (name "POWER") "1/8 W"))
      (libsource (lib "My_Library") (part "Resistor"))
    )
    (comp (ref "R88")
      (value "2.2K")
      (footprint "RES 0805 (2012X06L)")
      (description "Resistor")
      (fields (field (name "TOLERANCE") "5%") (field (name "POWER") "1/8 W"))
      (libsource (lib "My_Library") (part "Resistor"))
    )
    (comp (ref "R89")
      (value "2.2K")
      (footprint "RES 0805 (2012X06L)")
      (description "Resistor")
      (fields (field (name "TOLERANCE") "5%") (field (name "POWER") "1/8 W"))
      (libsource (lib "My_Library") (part "Resistor"))
    )
    (comp (ref "R90")
      (value "2.2K")
      (footprint "RES 0805 (2012X06L)")
      (description "Resistor")
      (fields (field (name "TOLERANCE") "5%") (field (name "POWER") "1/8 W"))
      (libsource (lib "My_Library") (part "Resistor"))
    )
    (comp (ref "R91")
      (value "3.3K")
      (footprint "RES 0805 (2012X06L)")
      (description "Resistor")
      (fields (field (name "TOLERANCE") "5%") (field (name "POWER") "1/8 W"))
      (libsource (lib "My_Library") (part "Resistor"))
    )
    (comp (ref "R92")
      (value "3.3K")
      (footprint "RES 0805 (2012X06L)")
      (description "Resistor")
      (fields (field (name "TOLERANCE") "5%") (field (name "POWER") "1/8 W"))
      (libsource (lib "My_Library") (part "Resistor"))
    )
    (comp (ref "R93")
      (value "3.3K")
      (footprint "RES 0805 (2012X06L)")
      (description "Resistor")
      (fields (field (name "TOLERANCE") "5%") (field (name "POWER") "1/8 W"))
      (libsource (lib "My_Library") (part "Resistor"))
    )
    (comp (ref "R94")
      (value "3.3K")
      (footprint "RES 0805 (2012X06L)")
      (description "Resistor")
      (fields (field (name "TOLERANCE") "5%") (field (name "POWER") "1/8 W"))
      (libsource (lib "My_Library") (part "Resistor"))
    )
    (comp (ref "R95")
      (value "150R")
      (footprint "RES 0805 (2012X06L)")
      (description "Resistor")
      (fields (field (name "TOLERANCE") "5%") (field (name "POWER") "1/8 W"))
      (libsource (lib "My_Library") (part "Resistor"))
    )
    (comp (ref "T1")
      (value "PHOENIX")
      (footprint "MSTB 2,5/2-G-5,08")
      (description "2 Pitch: 5.08 mm Color: green Contact surface: Tin Assembly")
      (fields
        (field (name "MANUFACTURER") "PHOENIX CONTACT")
        (field (name "VOLTAGE") "320 V")
        (field (name "DESIGNER") "ABBAS BASEREH")
      )
      (libsource (lib "Altium") (part "CON_Phoenix_MSTB_02"))
    )
    (comp (ref "TVS1")
      (value "PSM712")
      (footprint "SOT23_BEC_N")
      (libsource (lib "BeagleBoneBlack") (part "PSM712"))
    )
    (comp (ref "U1")
      (value "LM2596S-5")
      (footprint "*TO170P1435X465-6N")
      (fields (field (name "MF") "Texas Instruments"))
      (libsource (lib "LM2596S-3.3") (part "LM2596S-3.3"))
    )
    (comp (ref "U2")
      (value "MAX232")
      (footprint "NSO16_M")
      (description "+5V Powered, Multi-Channel RS-232 Driver/Receiver")
      (fields (field (name "COMPONENTAUTHOR") "Saeid Jorablo"))
      (libsource (lib "My_Library") (part "MAX232"))
    )
    (comp (ref "U3")
      (value "SP3485")
      (footprint "*SO08")
      (description "Low-Power, Slew-Rate-Limited RS-485/RS-422 Transceiver")
      (fields (field (name "PUBLISHER") "Altium Limited"))
      (libsource (lib "IC") (part "MAX485CPA"))
    )
    (comp (ref "U4")
      (value "HCPL2631S")
      (footprint "OPTO_HCPL2631S")
      (description "Optocoupler, Dual, Logic o/p")
      (fields (field (name "MF") "ON Semiconductor") (field (name "MP") "HCPL-2631.S"))
      (libsource (lib "HCPL2631S") (part "HCPL2631S"))
    )
    (comp (ref "U5")
      (value "HCPL2631S")
      (footprint "OPTO_HCPL2631S")
      (description "Optocoupler, Dual, Logic o/p")
      (fields (field (name "MF") "ON Semiconductor") (field (name "MP") "HCPL-2631.S"))
      (libsource (lib "HCPL2631S") (part "HCPL2631S"))
    )
    (comp (ref "U6")
      (value "HCPL2631S")
      (footprint "OPTO_HCPL2631S")
      (description "Optocoupler, Dual, Logic o/p")
      (fields (field (name "MF") "ON Semiconductor") (field (name "MP") "HCPL-2631.S"))
      (libsource (lib "HCPL2631S") (part "HCPL2631S"))
    )
    (comp (ref "U7")
      (value "HCPL2631S")
      (footprint "OPTO_HCPL2631S")
      (description "Optocoupler, Dual, Logic o/p")
      (fields (field (name "MF") "ON Semiconductor") (field (name "MP") "HCPL-2631.S"))
      (libsource (lib "HCPL2631S") (part "HCPL2631S"))
    )
    (comp (ref "U8")
      (value "HCPL2631S")
      (footprint "OPTO_HCPL2631S")
      (description "Optocoupler, Dual, Logic o/p")
      (fields (field (name "MF") "ON Semiconductor") (field (name "MP") "HCPL-2631.S"))
      (libsource (lib "HCPL2631S") (part "HCPL2631S"))
    )
    (comp (ref "U9")
      (value "HCPL2631S")
      (footprint "OPTO_HCPL2631S")
      (description "Optocoupler, Dual, Logic o/p")
      (fields (field (name "MF") "ON Semiconductor") (field (name "MP") "HCPL-2631.S"))
      (libsource (lib "HCPL2631S") (part "HCPL2631S"))
    )
    (comp (ref "U10")
      (value "HCPL2631S")
      (footprint "OPTO_HCPL2631S")
      (description "Optocoupler, Dual, Logic o/p")
      (fields (field (name "MF") "ON Semiconductor") (field (name "MP") "HCPL-2631.S"))
      (libsource (lib "HCPL2631S") (part "HCPL2631S"))
    )
    (comp (ref "U11")
      (value "HCPL2631S")
      (footprint "OPTO_HCPL2631S")
      (description "Optocoupler, Dual, Logic o/p")
      (fields (field (name "MF") "ON Semiconductor") (field (name "MP") "HCPL-2631.S"))
      (libsource (lib "HCPL2631S") (part "HCPL2631S"))
    )
    (comp (ref "U12")
      (value "MC3486DR")
      (footprint "SOIC127P600X175-16N")
      (libsource (lib "MC3486DR") (part "MC3486DR"))
    )
    (comp (ref "U13")
      (value "74HC14D,653")
      (footprint "SOIC127P600X175-14N")
      (description "Inverter IC 6 Channel Schmitt Trigger 14-SO")
      (fields (field (name "MF") "Nexperia USA"))
      (libsource (lib "74HC14D_653") (part "74HC14D,653"))
    )
    (comp (ref "UP1")
      (value "3V3")
      (footprint "SOT223")
      (description "x.x Volt, 800mA Low-Dropout Linear Regulator, 4-pin SOT-223")
      (fields (field (name "DESIGNER") "Ali Hafizi"))
      (libsource (lib "Altium") (part "AMS1117-x.x"))
    )
  )
  (nets
    (net (code "1") (name "/485_N") (class "Default")
      (node (ref "P1") (pin "9") (pinfunction "9_9") (pintype "passive"))
      (node (ref "R7") (pin "1") (pinfunction "1_1") (pintype "passive"))
    )
    (net (code "2") (name "/485_P") (class "Default")
      (node (ref "P1") (pin "4") (pinfunction "4_4") (pintype "passive"))
      (node (ref "R6") (pin "1") (pinfunction "1_1") (pintype "passive"))
    )
    (net (code "3") (name "/AI_1") (class "Default")
      (node (ref "P2") (pin "1") (pinfunction "1_1") (pintype "passive"))
      (node (ref "R8") (pin "2") (pinfunction "2_2") (pintype "passive"))
    )
    (net (code "4") (name "/AI_2") (class "Default")
      (node (ref "P2") (pin "2") (pinfunction "2_2") (pintype "passive"))
      (node (ref "R9") (pin "2") (pinfunction "2_2") (pintype "passive"))
    )
    (net (code "5") (name "/AI_3") (class "Default")
      (node (ref "P2") (pin "3") (pinfunction "3_3") (pintype "passive"))
      (node (ref "R10") (pin "2") (pinfunction "2_2") (pintype "passive"))
    )
    (net (code "6") (name "/AI_4") (class "Default")
      (node (ref "P2") (pin "4") (pinfunction "4_4") (pintype "passive"))
      (node (ref "R11") (pin "2") (pinfunction "2_2") (pintype "passive"))
    )
    (net (code "7") (name "/AI_5") (class "Default")
      (node (ref "P2") (pin "6") (pinfunction "6_6") (pintype "passive"))
      (node (ref "R12") (pin "2") (pinfunction "2_2") (pintype "passive"))
    )
    (net (code "8") (name "/AI_6") (class "Default")
      (node (ref "P2") (pin "7") (pinfunction "7_7") (pintype "passive"))
      (node (ref "R13") (pin "2") (pinfunction "2_2") (pintype "passive"))
    )
    (net (code "9") (name "/AI_7") (class "Default")
      (node (ref "P2") (pin "8") (pinfunction "8_8") (pintype "passive"))
      (node (ref "R14") (pin "2") (pinfunction "2_2") (pintype "passive"))
    )
    (net (code "10") (name "/Analouge_IN0") (class "Default")
      (node (ref "R15") (pin "2") (pinfunction "2_2") (pintype "passive"))
      (node (ref "R8") (pin "1") (pinfunction "1_1") (pintype "passive"))
    )
    (net (code "11") (name "/Analouge_IN1") (class "Default")
      (node (ref "R16") (pin "2") (pinfunction "2_2") (pintype "passive"))
      (node (ref "R9") (pin "1") (pinfunction "1_1") (pintype "passive"))
    )
    (net (code "12") (name "/Analouge_IN2") (class "Default")
      (node (ref "R10") (pin "1") (pinfunction "1_1") (pintype "passive"))
      (node (ref "R17") (pin "2") (pinfunction "2_2") (pintype "passive"))
    )
    (net (code "13") (name "/Analouge_IN3") (class "Default")
      (node (ref "R11") (pin "1") (pinfunction "1_1") (pintype "passive"))
      (node (ref "R18") (pin "2") (pinfunction "2_2") (pintype "passive"))
    )
    (net (code "14") (name "/Analouge_IN4") (class "Default")
      (node (ref "R12") (pin "1") (pinfunction "1_1") (pintype "passive"))
      (node (ref "R19") (pin "2") (pinfunction "2_2") (pintype "passive"))
    )
    (net (code "15") (name "/Analouge_IN5") (class "Default")
      (node (ref "R13") (pin "1") (pinfunction "1_1") (pintype "passive"))
      (node (ref "R20") (pin "2") (pinfunction "2_2") (pintype "passive"))
    )
    (net (code "16") (name "/Analouge_IN6") (class "Default")
      (node (ref "R14") (pin "1") (pinfunction "1_1") (pintype "passive"))
      (node (ref "R21") (pin "2") (pinfunction "2_2") (pintype "passive"))
    )
    (net (code "17") (name "/Direction_1") (class "Default")
      (node (ref "P3") (pin "6") (pinfunction "6_6") (pintype "passive"))
      (node (ref "Q5") (pin "3") (pinfunction "D_3") (pintype "passive"))
      (node (ref "R32") (pin "2") (pinfunction "2_2") (pintype "passive"))
    )
    (net (code "18") (name "/Direction_2") (class "Default")
      (node (ref "P3") (pin "7") (pinfunction "7_7") (pintype "passive"))
      (node (ref "Q6") (pin "3") (pinfunction "D_3") (pintype "passive"))
      (node (ref "R34") (pin "2") (pinfunction "2_2") (pintype "passive"))
    )
    (net (code "19") (name "/Direction_3") (class "Default")
      (node (ref "P3") (pin "8") (pinfunction "8_8") (pintype "passive"))
      (node (ref "Q7") (pin "3") (pinfunction "D_3") (pintype "passive"))
      (node (ref "R36") (pin "2") (pinfunction "2_2") (pintype "passive"))
    )
    (net (code "20") (name "/Direction_4") (class "Default")
      (node (ref "P3") (pin "9") (pinfunction "9_9") (pintype "passive"))
      (node (ref "Q8") (pin "3") (pinfunction "D_3") (pintype "passive"))
      (node (ref "R38") (pin "2") (pinfunction "2_2") (pintype "passive"))
    )
    (net (code "21") (name "/ENC1_A") (class "Default")
      (node (ref "U12") (pin "5") (pinfunction "2Y_5") (pintype "bidirectional"))
      (node (ref "U13") (pin "1") (pinfunction "1A_1") (pintype "input"))
    )
    (net (code "22") (name "/ENC1_A_N") (class "Default")
      (node (ref "C28") (pin "2") (pinfunction "-_2") (pintype "passive"))
      (node (ref "P6") (pin "7") (pinfunction "7_7") (pintype "passive"))
      (node (ref "R72") (pin "2") (pinfunction "2_2") (pintype "passive"))
      (node (ref "R79") (pin "2") (pinfunction "2_2") (pintype "passive"))
      (node (ref "R80") (pin "2") (pinfunction "2_2") (pintype "passive"))
      (node (ref "U12") (pin "7") (pinfunction "2B_7") (pintype "bidirectional"))
    )
    (net (code "23") (name "/ENC1_A_P") (class "Default")
      (node (ref "C27") (pin "1") (pinfunction "+_1") (pintype "passive"))
      (node (ref "P6") (pin "6") (pinfunction "6_6") (pintype "passive"))
      (node (ref "R72") (pin "1") (pinfunction "1_1") (pintype "passive"))
      (node (ref "R78") (pin "2") (pinfunction "2_2") (pintype "passive"))
      (node (ref "U12") (pin "6") (pinfunction "2A_6") (pintype "bidirectional"))
    )
    (net (code "24") (name "/ENC1_B") (class "Default")
      (node (ref "U12") (pin "3") (pinfunction "1Y_3") (pintype "bidirectional"))
      (node (ref "U13") (pin "3") (pinfunction "2A_3") (pintype "input"))
    )
    (net (code "25") (name "/ENC1_B_N") (class "Default")
      (node (ref "C25") (pin "1") (pinfunction "+_1") (pintype "passive"))
      (node (ref "P6") (pin "2") (pinfunction "2_2") (pintype "passive"))
      (node (ref "R71") (pin "1") (pinfunction "1_1") (pintype "passive"))
      (node (ref "R75") (pin "2") (pinfunction "2_2") (pintype "passive"))
      (node (ref "R76") (pin "2") (pinfunction "2_2") (pintype "passive"))
      (node (ref "U12") (pin "1") (pinfunction "1B_1") (pintype "bidirectional"))
    )
    (net (code "26") (name "/ENC1_B_P") (class "Default")
      (node (ref "C26") (pin "2") (pinfunction "-_2") (pintype "passive"))
      (node (ref "P6") (pin "1") (pinfunction "1_1") (pintype "passive"))
      (node (ref "R71") (pin "2") (pinfunction "2_2") (pintype "passive"))
      (node (ref "R77") (pin "2") (pinfunction "2_2") (pintype "passive"))
      (node (ref "U12") (pin "2") (pinfunction "1A_2") (pintype "bidirectional"))
    )
    (net (code "27") (name "/ENC2_A") (class "Default")
      (node (ref "U12") (pin "13") (pinfunction "4Y_13") (pintype "bidirectional"))
      (node (ref "U13") (pin "11") (pinfunction "5A_11") (pintype "input"))
    )
    (net (code "28") (name "/ENC2_A_N") (class "Default")
      (node (ref "C32") (pin "1") (pinfunction "+_1") (pintype "passive"))
      (node (ref "P6") (pin "3") (pinfunction "3_3") (pintype "passive"))
      (node (ref "R74") (pin "1") (pinfunction "1_1") (pintype "passive"))
      (node (ref "R85") (pin "2") (pinfunction "2_2") (pintype "passive"))
      (node (ref "R86") (pin "2") (pinfunction "2_2") (pintype "passive"))
      (node (ref "U12") (pin "15") (pinfunction "4B_15") (pintype "bidirectional"))
    )
    (net (code "29") (name "/ENC2_A_P") (class "Default")
      (node (ref "C31") (pin "2") (pinfunction "-_2") (pintype "passive"))
      (node (ref "P6") (pin "4") (pinfunction "4_4") (pintype "passive"))
      (node (ref "R74") (pin "2") (pinfunction "2_2") (pintype "passive"))
      (node (ref "R84") (pin "2") (pinfunction "2_2") (pintype "passive"))
      (node (ref "U12") (pin "14") (pinfunction "4A_14") (pintype "bidirectional"))
    )
    (net (code "30") (name "/ENC2_B") (class "Default")
      (node (ref "U12") (pin "11") (pinfunction "3Y_11") (pintype "bidirectional"))
      (node (ref "U13") (pin "13") (pinfunction "6A_13") (pintype "input"))
    )
    (net (code "31") (name "/ENC2_B_N") (class "Default")
      (node (ref "C29") (pin "2") (pinfunction "-_2") (pintype "passive"))
      (node (ref "P6") (pin "8") (pinfunction "8_8") (pintype "passive"))
      (node (ref "R73") (pin "2") (pinfunction "2_2") (pintype "passive"))
      (node (ref "R82") (pin "2") (pinfunction "2_2") (pintype "passive"))
      (node (ref "R83") (pin "2") (pinfunction "2_2") (pintype "passive"))
      (node (ref "U12") (pin "9") (pinfunction "3B_9") (pintype "bidirectional"))
    )
    (net (code "32") (name "/ENC2_B_P") (class "Default")
      (node (ref "C30") (pin "1") (pinfunction "+_1") (pintype "passive"))
      (node (ref "P6") (pin "9") (pinfunction "9_9") (pintype "passive"))
      (node (ref "R73") (pin "1") (pinfunction "1_1") (pintype "passive"))
      (node (ref "R81") (pin "2") (pinfunction "2_2") (pintype "passive"))
      (node (ref "U12") (pin "10") (pinfunction "3A_10") (pintype "bidirectional"))
    )
    (net (code "33") (name "/GPIO1_2") (class "Default")
      (node (ref "Q6") (pin "2") (pinfunction "S_2") (pintype "passive"))
      (node (ref "R33") (pin "2") (pinfunction "2_2") (pintype "passive"))
    )
    (net (code "34") (name "/GPIO1_3") (class "Default")
      (node (ref "Q7") (pin "2") (pinfunction "S_2") (pintype "passive"))
      (node (ref "R35") (pin "2") (pinfunction "2_2") (pintype "passive"))
    )
    (net (code "35") (name "/GPIO1_6") (class "Default")
      (node (ref "Q5") (pin "2") (pinfunction "S_2") (pintype "passive"))
      (node (ref "R31") (pin "2") (pinfunction "2_2") (pintype "passive"))
    )
    (net (code "36") (name "/GPIO1_7") (class "Default")
      (node (ref "Q8") (pin "2") (pinfunction "S_2") (pintype "passive"))
      (node (ref "R37") (pin "2") (pinfunction "2_2") (pintype "passive"))
    )
    (net (code "37") (name "/GPIO1_16 (485_EN)") (class "Default")
      (node (ref "U3") (pin "2") (pinfunction "~{RE}_2") (pintype "input"))
      (node (ref "U3") (pin "3") (pinfunction "DE_3") (pintype "input"))
    )
    (net (code "38") (name "/HS_IN0") (class "Default")
      (node (ref "P5") (pin "1") (pinfunction "1_1") (pintype "passive"))
      (node (ref "R55") (pin "1") (pinfunction "1_1") (pintype "passive"))
    )
    (net (code "39") (name "/HS_IN1") (class "Default")
      (node (ref "P5") (pin "2") (pinfunction "2_2") (pintype "passive"))
      (node (ref "R56") (pin "1") (pinfunction "1_1") (pintype "passive"))
    )
    (net (code "40") (name "/HS_IN2") (class "Default")
      (node (ref "P5") (pin "3") (pinfunction "3_3") (pintype "passive"))
      (node (ref "R57") (pin "1") (pinfunction "1_1") (pintype "passive"))
    )
    (net (code "41") (name "/HS_IN3") (class "Default")
      (node (ref "P5") (pin "4") (pinfunction "4_4") (pintype "passive"))
      (node (ref "R58") (pin "1") (pinfunction "1_1") (pintype "passive"))
    )
    (net (code "42") (name "/HS_IN4") (class "Default")
      (node (ref "P5") (pin "6") (pinfunction "6_6") (pintype "passive"))
      (node (ref "R59") (pin "1") (pinfunction "1_1") (pintype "passive"))
    )
    (net (code "43") (name "/HS_IN5") (class "Default")
      (node (ref "P5") (pin "7") (pinfunction "7_7") (pintype "passive"))
      (node (ref "R60") (pin "1") (pinfunction "1_1") (pintype "passive"))
    )
    (net (code "44") (name "/HS_IN6") (class "Default")
      (node (ref "P5") (pin "8") (pinfunction "8_8") (pintype "passive"))
      (node (ref "R61") (pin "1") (pinfunction "1_1") (pintype "passive"))
    )
    (net (code "45") (name "/HS_IN7") (class "Default")
      (node (ref "P5") (pin "9") (pinfunction "9_9") (pintype "passive"))
      (node (ref "R62") (pin "1") (pinfunction "1_1") (pintype "passive"))
    )
    (net (code "46") (name "/HS_OUT0") (class "Default")
      (node (ref "P4") (pin "1") (pinfunction "1_1") (pintype "passive"))
      (node (ref "R41") (pin "1") (pinfunction "1_1") (pintype "passive"))
      (node (ref "U4") (pin "7") (pinfunction "V01_7") (pintype "output"))
    )
    (net (code "47") (name "/HS_OUT1") (class "Default")
      (node (ref "P4") (pin "2") (pinfunction "2_2") (pintype "passive"))
      (node (ref "R45") (pin "1") (pinfunction "1_1") (pintype "passive"))
      (node (ref "U5") (pin "7") (pinfunction "V01_7") (pintype "output"))
    )
    (net (code "48") (name "/HS_OUT2") (class "Default")
      (node (ref "P4") (pin "3") (pinfunction "3_3") (pintype "passive"))
      (node (ref "R49") (pin "1") (pinfunction "1_1") (pintype "passive"))
      (node (ref "U6") (pin "7") (pinfunction "V01_7") (pintype "output"))
    )
    (net (code "49") (name "/HS_OUT3") (class "Default")
      (node (ref "P4") (pin "4") (pinfunction "4_4") (pintype "passive"))
      (node (ref "R53") (pin "1") (pinfunction "1_1") (pintype "passive"))
      (node (ref "U7") (pin "7") (pinfunction "V01_7") (pintype "output"))
    )
    (net (code "50") (name "/HS_OUT4") (class "Default")
      (node (ref "P4") (pin "6") (pinfunction "6_6") (pintype "passive"))
      (node (ref "R42") (pin "1") (pinfunction "1_1") (pintype "passive"))
      (node (ref "U4") (pin "6") (pinfunction "V02_6") (pintype "output"))
    )
    (net (code "51") (name "/HS_OUT5") (class "Default")
      (node (ref "P4") (pin "7") (pinfunction "7_7") (pintype "passive"))
      (node (ref "R46") (pin "1") (pinfunction "1_1") (pintype "passive"))
      (node (ref "U5") (pin "6") (pinfunction "V02_6") (pintype "output"))
    )
    (net (code "52") (name "/HS_OUT6") (class "Default")
      (node (ref "P4") (pin "8") (pinfunction "8_8") (pintype "passive"))
      (node (ref "R50") (pin "1") (pinfunction "1_1") (pintype "passive"))
      (node (ref "U6") (pin "6") (pinfunction "V02_6") (pintype "output"))
    )
    (net (code "53") (name "/HS_OUT7") (class "Default")
      (node (ref "P4") (pin "9") (pinfunction "9_9") (pintype "passive"))
      (node (ref "R54") (pin "1") (pinfunction "1_1") (pintype "passive"))
      (node (ref "U7") (pin "6") (pinfunction "V02_6") (pintype "output"))
    )
    (net (code "54") (name "/PRU0_R30OUT_2") (class "Default")
      (node (ref "R39") (pin "1") (pinfunction "1_1") (pintype "passive"))
    )
    (net (code "55") (name "/PRU0_R30OUT_5") (class "Default")
      (node (ref "R43") (pin "1") (pinfunction "1_1") (pintype "passive"))
    )
    (net (code "56") (name "/PRU0_R30OUT_7") (class "Default")
      (node (ref "R47") (pin "1") (pinfunction "1_1") (pintype "passive"))
    )
    (net (code "57") (name "/PRU1_R30OUT_8") (class "Default")
      (node (ref "R51") (pin "1") (pinfunction "1_1") (pintype "passive"))
    )
    (net (code "58") (name "/PRU1_R30OUT_9") (class "Default")
      (node (ref "R40") (pin "1") (pinfunction "1_1") (pintype "passive"))
    )
    (net (code "59") (name "/PRU1_R30OUT_10") (class "Default")
      (node (ref "R44") (pin "1") (pinfunction "1_1") (pintype "passive"))
    )
    (net (code "60") (name "/PRU1_R30OUT_12") (class "Default")
      (node (ref "R48") (pin "1") (pinfunction "1_1") (pintype "passive"))
    )
    (net (code "61") (name "/PRU1_R30OUT_13") (class "Default")
      (node (ref "R52") (pin "1") (pinfunction "1_1") (pintype "passive"))
    )
    (net (code "62") (name "/PRU1_R31IN_0") (class "Default")
      (node (ref "R63") (pin "1") (pinfunction "1_1") (pintype "passive"))
      (node (ref "U8") (pin "7") (pinfunction "V01_7") (pintype "output"))
    )
    (net (code "63") (name "/PRU1_R31IN_1") (class "Default")
      (node (ref "R64") (pin "1") (pinfunction "1_1") (pintype "passive"))
      (node (ref "U8") (pin "6") (pinfunction "V02_6") (pintype "output"))
    )
    (net (code "64") (name "/PRU1_R31IN_2") (class "Default")
      (node (ref "R65") (pin "1") (pinfunction "1_1") (pintype "passive"))
      (node (ref "U9") (pin "7") (pinfunction "V01_7") (pintype "output"))
    )
    (net (code "65") (name "/PRU1_R31IN_3") (class "Default")
      (node (ref "R66") (pin "1") (pinfunction "1_1") (pintype "passive"))
      (node (ref "U9") (pin "6") (pinfunction "V02_6") (pintype "output"))
    )
    (net (code "66") (name "/PRU1_R31IN_4") (class "Default")
      (node (ref "R67") (pin "1") (pinfunction "1_1") (pintype "passive"))
      (node (ref "U10") (pin "7") (pinfunction "V01_7") (pintype "output"))
    )
    (net (code "67") (name "/PRU1_R31IN_5") (class "Default")
      (node (ref "R68") (pin "1") (pinfunction "1_1") (pintype "passive"))
      (node (ref "U10") (pin "6") (pinfunction "V02_6") (pintype "output"))
    )
    (net (code "68") (name "/PRU1_R31IN_6") (class "Default")
      (node (ref "R69") (pin "1") (pinfunction "1_1") (pintype "passive"))
      (node (ref "U11") (pin "7") (pinfunction "V01_7") (pintype "output"))
    )
    (net (code "69") (name "/PRU1_R31IN_7") (class "Default")
      (node (ref "R70") (pin "1") (pinfunction "1_1") (pintype "passive"))
      (node (ref "U11") (pin "6") (pinfunction "V02_6") (pintype "output"))
    )
    (net (code "70") (name "/Pulse_1") (class "Default")
      (node (ref "P3") (pin "1") (pinfunction "1_1") (pintype "passive"))
      (node (ref "Q1") (pin "3") (pinfunction "D_3") (pintype "passive"))
      (node (ref "R24") (pin "2") (pinfunction "2_2") (pintype "passive"))
    )
    (net (code "71") (name "/Pulse_2") (class "Default")
      (node (ref "P3") (pin "2") (pinfunction "2_2") (pintype "passive"))
      (node (ref "Q2") (pin "3") (pinfunction "D_3") (pintype "passive"))
      (node (ref "R26") (pin "2") (pinfunction "2_2") (pintype "passive"))
    )
    (net (code "72") (name "/Pulse_3") (class "Default")
      (node (ref "P3") (pin "3") (pinfunction "3_3") (pintype "passive"))
      (node (ref "Q3") (pin "3") (pinfunction "D_3") (pintype "passive"))
      (node (ref "R28") (pin "2") (pinfunction "2_2") (pintype "passive"))
    )
    (net (code "73") (name "/Pulse_4") (class "Default")
      (node (ref "P3") (pin "4") (pinfunction "4_4") (pintype "passive"))
      (node (ref "Q4") (pin "3") (pinfunction "D_3") (pintype "passive"))
      (node (ref "R30") (pin "2") (pinfunction "2_2") (pintype "passive"))
    )
    (net (code "74") (name "/QEP1_A") (class "Default")
      (node (ref "R87") (pin "2") (pinfunction "2_2") (pintype "passive"))
      (node (ref "R94") (pin "1") (pinfunction "1_1") (pintype "passive"))
    )
    (net (code "75") (name "/QEP1_B") (class "Default")
      (node (ref "R88") (pin "2") (pinfunction "2_2") (pintype "passive"))
      (node (ref "R93") (pin "1") (pinfunction "1_1") (pintype "passive"))
    )
    (net (code "76") (name "/QEP2_A") (class "Default")
      (node (ref "R89") (pin "2") (pinfunction "2_2") (pintype "passive"))
      (node (ref "R92") (pin "1") (pinfunction "1_1") (pintype "passive"))
    )
    (net (code "77") (name "/QEP2_B") (class "Default")
      (node (ref "R90") (pin "2") (pinfunction "2_2") (pintype "passive"))
      (node (ref "R91") (pin "1") (pinfunction "1_1") (pintype "passive"))
    )
    (net (code "78") (name "/RX1") (class "Default")
      (node (ref "P1") (pin "3") (pinfunction "3_3") (pintype "passive"))
      (node (ref "R1") (pin "1") (pinfunction "1_1") (pintype "passive"))
    )
    (net (code "79") (name "/SPI0_CS0") (class "Default")
      (node (ref "P1") (pin "6") (pinfunction "6_6") (pintype "passive+no_connect"))
    )
    (net (code "80") (name "/SPI0_D0") (class "Default")
      (node (ref "P1") (pin "8") (pinfunction "8_8") (pintype "passive+no_connect"))
    )
    (net (code "81") (name "/SPI0_D1") (class "Default")
      (node (ref "P1") (pin "1") (pinfunction "1_1") (pintype "passive+no_connect"))
    )
    (net (code "82") (name "/SPI0_SCLK") (class "Default")
      (node (ref "P1") (pin "7") (pinfunction "7_7") (pintype "passive+no_connect"))
    )
    (net (code "83") (name "/TIMER4") (class "Default")
      (node (ref "Q1") (pin "2") (pinfunction "S_2") (pintype "passive"))
      (node (ref "R23") (pin "2") (pinfunction "2_2") (pintype "passive"))
    )
    (net (code "84") (name "/TIMER5") (class "Default")
      (node (ref "Q2") (pin "2") (pinfunction "S_2") (pintype "passive"))
      (node (ref "R25") (pin "2") (pinfunction "2_2") (pintype "passive"))
    )
    (net (code "85") (name "/TIMER6") (class "Default")
      (node (ref "Q3") (pin "2") (pinfunction "S_2") (pintype "passive"))
      (node (ref "R27") (pin "2") (pinfunction "2_2") (pintype "passive"))
    )
    (net (code "86") (name "/TIMER7") (class "Default")
      (node (ref "Q4") (pin "2") (pinfunction "S_2") (pintype "passive"))
      (node (ref "R29") (pin "2") (pinfunction "2_2") (pintype "passive"))
    )
    (net (code "87") (name "/TX1") (class "Default")
      (node (ref "P1") (pin "2") (pinfunction "2_2") (pintype "passive"))
      (node (ref "R2") (pin "1") (pinfunction "1_1") (pintype "passive"))
    )
    (net (code "88") (name "/UART1_RXD") (class "Default")
      (node (ref "U2") (pin "12") (pinfunction "R1OUT_12") (pintype "passive"))
    )
    (net (code "89") (name "/UART1_TXD") (class "Default")
      (node (ref "U2") (pin "11") (pinfunction "T1IN_11") (pintype "passive"))
    )
    (net (code "90") (name "/UART4_RXD") (class "Default")
      (node (ref "U3") (pin "1") (pinfunction "RO_1") (pintype "output"))
    )
    (net (code "91") (name "/UART4_TXD") (class "Default")
      (node (ref "U3") (pin "4") (pinfunction "DI_4") (pintype "input"))
    )
    (net (code "92") (name "3V3") (class "Default")
      (node (ref "C10") (pin "2") (pinfunction "-_2") (pintype "passive"))
      (node (ref "C13") (pin "1") (pinfunction "+_1") (pintype "passive"))
      (node (ref "C14") (pin "2") (pinfunction "P_2") (pintype "passive"))
      (node (ref "Q1") (pin "1") (pinfunction "G_1") (pintype "passive"))
      (node (ref "Q2") (pin "1") (pinfunction "G_1") (pintype "passive"))
      (node (ref "Q3") (pin "1") (pinfunction "G_1") (pintype "passive"))
      (node (ref "Q4") (pin "1") (pinfunction "G_1") (pintype "passive"))
      (node (ref "Q5") (pin "1") (pinfunction "G_1") (pintype "passive"))
      (node (ref "Q6") (pin "1") (pinfunction "G_1") (pintype "passive"))
      (node (ref "Q7") (pin "1") (pinfunction "G_1") (pintype "passive"))
      (node (ref "Q8") (pin "1") (pinfunction "G_1") (pintype "passive"))
      (node (ref "R22") (pin "1") (pinfunction "1_1") (pintype "passive"))
      (node (ref "R23") (pin "1") (pinfunction "1_1") (pintype "passive"))
      (node (ref "R25") (pin "1") (pinfunction "1_1") (pintype "passive"))
      (node (ref "R27") (pin "1") (pinfunction "1_1") (pintype "passive"))
      (node (ref "R29") (pin "1") (pinfunction "1_1") (pintype "passive"))
      (node (ref "R3") (pin "1") (pinfunction "1_1") (pintype "passive"))
      (node (ref "R31") (pin "1") (pinfunction "1_1") (pintype "passive"))
      (node (ref "R33") (pin "1") (pinfunction "1_1") (pintype "passive"))
      (node (ref "R35") (pin "1") (pinfunction "1_1") (pintype "passive"))
      (node (ref "R37") (pin "1") (pinfunction "1_1") (pintype "passive"))
      (node (ref "R63") (pin "2") (pinfunction "2_2") (pintype "passive"))
      (node (ref "R64") (pin "2") (pinfunction "2_2") (pintype "passive"))
      (node (ref "R65") (pin "2") (pinfunction "2_2") (pintype "passive"))
      (node (ref "R66") (pin "2") (pinfunction "2_2") (pintype "passive"))
      (node (ref "R67") (pin "2") (pinfunction "2_2") (pintype "passive"))
      (node (ref "R68") (pin "2") (pinfunction "2_2") (pintype "passive"))
      (node (ref "R69") (pin "2") (pinfunction "2_2") (pintype "passive"))
      (node (ref "R70") (pin "2") (pinfunction "2_2") (pintype "passive"))
      (node (ref "R95") (pin "2") (pinfunction "2_2") (pintype "passive"))
      (node (ref "U2") (pin "16") (pinfunction "VCC_16") (pintype "power_in"))
      (node (ref "U4") (pin "1") (pinfunction "VF1+_1") (pintype "input"))
      (node (ref "U4") (pin "4") (pinfunction "VF2+_4") (pintype "input"))
      (node (ref "U5") (pin "1") (pinfunction "VF1+_1") (pintype "input"))
      (node (ref "U5") (pin "4") (pinfunction "VF2+_4") (pintype "input"))
      (node (ref "U6") (pin "1") (pinfunction "VF1+_1") (pintype "input"))
      (node (ref "U6") (pin "4") (pinfunction "VF2+_4") (pintype "input"))
      (node (ref "U7") (pin "1") (pinfunction "VF1+_1") (pintype "input"))
      (node (ref "U7") (pin "4") (pinfunction "VF2+_4") (pintype "input"))
      (node (ref "UP1") (pin "2") (pinfunction "OUT_2") (pintype "power_in"))
      (node (ref "UP1") (pin "4") (pinfunction "TAB_4") (pintype "power_in"))
    )
    (net (code "93") (name "24V") (class "Default")
      (node (ref "C1") (pin "1") (pinfunction "+_1") (pintype "passive"))
      (node (ref "C2") (pin "2") (pinfunction "P_2") (pintype "passive"))
      (node (ref "D1") (pin "2") (pinfunction "K_2") (pintype "passive"))
      (node (ref "D2") (pin "2") (pinfunction "K_2") (pintype "passive"))
      (node (ref "R41") (pin "2") (pinfunction "2_2") (pintype "passive"))
      (node (ref "R42") (pin "2") (pinfunction "2_2") (pintype "passive"))
      (node (ref "R45") (pin "2") (pinfunction "2_2") (pintype "passive"))
      (node (ref "R46") (pin "2") (pinfunction "2_2") (pintype "passive"))
      (node (ref "R49") (pin "2") (pinfunction "2_2") (pintype "passive"))
      (node (ref "R50") (pin "2") (pinfunction "2_2") (pintype "passive"))
      (node (ref "R53") (pin "2") (pinfunction "2_2") (pintype "passive"))
      (node (ref "R54") (pin "2") (pinfunction "2_2") (pintype "passive"))
      (node (ref "U1") (pin "1") (pinfunction "VIN_1") (pintype "power_in"))
      (node (ref "U10") (pin "1") (pinfunction "VF1+_1") (pintype "input"))
      (node (ref "U10") (pin "4") (pinfunction "VF2+_4") (pintype "input"))
      (node (ref "U11") (pin "1") (pinfunction "VF1+_1") (pintype "input"))
      (node (ref "U11") (pin "4") (pinfunction "VF2+_4") (pintype "input"))
      (node (ref "U8") (pin "1") (pinfunction "VF1+_1") (pintype "input"))
      (node (ref "U8") (pin "4") (pinfunction "VF2+_4") (pintype "input"))
      (node (ref "U9") (pin "1") (pinfunction "VF1+_1") (pintype "input"))
      (node (ref "U9") (pin "4") (pinfunction "VF2+_4") (pintype "input"))
    )
    (net (code "94") (name "DGND") (class "Default")
      (node (ref "C1") (pin "2") (pinfunction "-_2") (pintype "passive"))
      (node (ref "C10") (pin "1") (pinfunction "+_1") (pintype "passive"))
      (node (ref "C11") (pin "1") (pinfunction "N_1") (pintype "passive"))
      (node (ref "C12") (pin "2") (pinfunction "-_2") (pintype "passive"))
      (node (ref "C13") (pin "2") (pinfunction "-_2") (pintype "passive"))
      (node (ref "C14") (pin "1") (pinfunction "N_1") (pintype "passive"))
      (node (ref "C15") (pin "1") (pinfunction "+_1") (pintype "passive"))
      (node (ref "C16") (pin "1") (pinfunction "+_1") (pintype "passive"))
      (node (ref "C17") (pin "1") (pinfunction "+_1") (pintype "passive"))
      (node (ref "C18") (pin "1") (pinfunction "+_1") (pintype "passive"))
      (node (ref "C19") (pin "1") (pinfunction "+_1") (pintype "passive"))
      (node (ref "C2") (pin "1") (pinfunction "N_1") (pintype "passive"))
      (node (ref "C20") (pin "1") (pinfunction "+_1") (pintype "passive"))
      (node (ref "C21") (pin "1") (pinfunction "+_1") (pintype "passive"))
      (node (ref "C22") (pin "1") (pinfunction "+_1") (pintype "passive"))
      (node (ref "C23") (pin "1") (pinfunction "+_1") (pintype "passive"))
      (node (ref "C24") (pin "1") (pinfunction "+_1") (pintype "passive"))
      (node (ref "C25") (pin "2") (pinfunction "-_2") (pintype "passive"))
      (node (ref "C26") (pin "1") (pinfunction "+_1") (pintype "passive"))
      (node (ref "C27") (pin "2") (pinfunction "-_2") (pintype "passive"))
      (node (ref "C28") (pin "1") (pinfunction "+_1") (pintype "passive"))
      (node (ref "C29") (pin "1") (pinfunction "+_1") (pintype "passive"))
      (node (ref "C3") (pin "1") (pinfunction "N_1") (pintype "passive"))
      (node (ref "C30") (pin "2") (pinfunction "-_2") (pintype "passive"))
      (node (ref "C31") (pin "1") (pinfunction "+_1") (pintype "passive"))
      (node (ref "C32") (pin "2") (pinfunction "-_2") (pintype "passive"))
      (node (ref "C33") (pin "1") (pinfunction "+_1") (pintype "passive"))
      (node (ref "C34") (pin "1") (pinfunction "+_1") (pintype "passive"))
      (node (ref "C4") (pin "1") (pinfunction "N_1") (pintype "passive"))
      (node (ref "C5") (pin "2") (pinfunction "-_2") (pintype "passive"))
      (node (ref "C8") (pin "2") (pinfunction "-_2") (pintype "passive"))
      (node (ref "C9") (pin "2") (pinfunction "-_2") (pintype "passive"))
      (node (ref "D3") (pin "1") (pinfunction "A_1") (pintype "passive"))
      (node (ref "LED0") (pin "2") (pinfunction "K_2") (pintype "passive"))
      (node (ref "P1") (pin "10") (pinfunction "MH1_10") (pintype "passive"))
      (node (ref "P1") (pin "11") (pinfunction "MH2_11") (pintype "passive"))
      (node (ref "P1") (pin "5") (pinfunction "5_5") (pintype "passive"))
      (node (ref "P3") (pin "10") (pinfunction "MH1_10") (pintype "passive"))
      (node (ref "P3") (pin "11") (pinfunction "MH2_11") (pintype "passive"))
      (node (ref "P3") (pin "5") (pinfunction "5_5") (pintype "passive"))
      (node (ref "P4") (pin "10") (pinfunction "MH1_10") (pintype "passive"))
      (node (ref "P4") (pin "11") (pinfunction "MH2_11") (pintype "passive"))
      (node (ref "P4") (pin "5") (pinfunction "5_5") (pintype "passive"))
      (node (ref "P5") (pin "10") (pinfunction "MH1_10") (pintype "passive"))
      (node (ref "P5") (pin "11") (pinfunction "MH2_11") (pintype "passive"))
      (node (ref "P5") (pin "5") (pinfunction "5_5") (pintype "passive"))
      (node (ref "P6") (pin "10") (pinfunction "MH1_10") (pintype "passive"))
      (node (ref "P6") (pin "11") (pinfunction "MH2_11") (pintype "passive"))
      (node (ref "P6") (pin "5") (pinfunction "5_5") (pintype "passive"))
      (node (ref "R5") (pin "2") (pinfunction "2_2") (pintype "passive"))
      (node (ref "R75") (pin "1") (pinfunction "1_1") (pintype "passive"))
      (node (ref "R80") (pin "1") (pinfunction "1_1") (pintype "passive"))
      (node (ref "R83") (pin "1") (pinfunction "1_1") (pintype "passive"))
      (node (ref "R86") (pin "1") (pinfunction "1_1") (pintype "passive"))
      (node (ref "R91") (pin "2") (pinfunction "2_2") (pintype "passive"))
      (node (ref "R92") (pin "2") (pinfunction "2_2") (pintype "passive"))
      (node (ref "R93") (pin "2") (pinfunction "2_2") (pintype "passive"))
      (node (ref "R94") (pin "2") (pinfunction "2_2") (pintype "passive"))
      (node (ref "T1") (pin "1") (pinfunction "1_1") (pintype "passive"))
      (node (ref "TVS1") (pin "3") (pinfunction "K_3") (pintype "passive"))
      (node (ref "U1") (pin "3") (pinfunction "GND_3") (pintype "passive"))
      (node (ref "U1") (pin "5") (pinfunction "~{ON}/OFF_5") (pintype "input"))
      (node (ref "U1") (pin "6") (pinfunction "Bulk_6") (pintype "passive"))
      (node (ref "U10") (pin "5") (pinfunction "GND_5") (pintype "power_in"))
      (node (ref "U11") (pin "5") (pinfunction "GND_5") (pintype "power_in"))
      (node (ref "U12") (pin "8") (pinfunction "GND_8") (pintype "power_in"))
      (node (ref "U13") (pin "7") (pinfunction "GND_7") (pintype "passive"))
      (node (ref "U2") (pin "15") (pinfunction "GND_15") (pintype "power_in"))
      (node (ref "U3") (pin "5") (pinfunction "GND3.3_5") (pintype "power_in"))
      (node (ref "U4") (pin "5") (pinfunction "GND_5") (pintype "power_in"))
      (node (ref "U5") (pin "5") (pinfunction "GND_5") (pintype "power_in"))
      (node (ref "U6") (pin "5") (pinfunction "GND_5") (pintype "power_in"))
      (node (ref "U7") (pin "5") (pinfunction "GND_5") (pintype "power_in"))
      (node (ref "U8") (pin "5") (pinfunction "GND_5") (pintype "power_in"))
      (node (ref "U9") (pin "5") (pinfunction "GND_5") (pintype "power_in"))
      (node (ref "UP1") (pin "1") (pinfunction "GND_1") (pintype "power_in"))
    )
    (net (code "95") (name "GND_ADC") (class "Default")
      (node (ref "P2") (pin "10") (pinfunction "MH1_10") (pintype "passive"))
      (node (ref "P2") (pin "11") (pinfunction "MH2_11") (pintype "passive"))
      (node (ref "P2") (pin "5") (pinfunction "5_5") (pintype "passive"))
      (node (ref "R15") (pin "1") (pinfunction "1_1") (pintype "passive"))
      (node (ref "R16") (pin "1") (pinfunction "1_1") (pintype "passive"))
      (node (ref "R17") (pin "1") (pinfunction "1_1") (pintype "passive"))
      (node (ref "R18") (pin "1") (pinfunction "1_1") (pintype "passive"))
      (node (ref "R19") (pin "1") (pinfunction "1_1") (pintype "passive"))
      (node (ref "R20") (pin "1") (pinfunction "1_1") (pintype "passive"))
      (node (ref "R21") (pin "1") (pinfunction "1_1") (pintype "passive"))
    )
    (net (code "96") (name "Net-(C6-+)") (class "Default")
      (node (ref "C6") (pin "1") (pinfunction "+_1") (pintype "passive"))
      (node (ref "U2") (pin "5") (pinfunction "C2-_5") (pintype "passive"))
    )
    (net (code "97") (name "Net-(C6--)") (class "Default")
      (node (ref "C6") (pin "2") (pinfunction "-_2") (pintype "passive"))
      (node (ref "U2") (pin "4") (pinfunction "C2+_4") (pintype "passive"))
    )
    (net (code "98") (name "Net-(C7-+)") (class "Default")
      (node (ref "C7") (pin "1") (pinfunction "+_1") (pintype "passive"))
      (node (ref "U2") (pin "3") (pinfunction "C1-_3") (pintype "passive"))
    )
    (net (code "99") (name "Net-(C7--)") (class "Default")
      (node (ref "C7") (pin "2") (pinfunction "-_2") (pintype "passive"))
      (node (ref "U2") (pin "1") (pinfunction "C1+_1") (pintype "passive"))
    )
    (net (code "100") (name "Net-(C8-+)") (class "Default")
      (node (ref "C8") (pin "1") (pinfunction "+_1") (pintype "passive"))
      (node (ref "U2") (pin "6") (pinfunction "V-_6") (pintype "passive"))
    )
    (net (code "101") (name "Net-(C9-+)") (class "Default")
      (node (ref "C9") (pin "1") (pinfunction "+_1") (pintype "passive"))
      (node (ref "U2") (pin "2") (pinfunction "V+_2") (pintype "passive"))
    )
    (net (code "102") (name "Net-(C15--)") (class "Default")
      (node (ref "C15") (pin "2") (pinfunction "-_2") (pintype "passive"))
      (node (ref "C16") (pin "2") (pinfunction "-_2") (pintype "passive"))
      (node (ref "R22") (pin "2") (pinfunction "2_2") (pintype "passive"))
      (node (ref "U3") (pin "8") (pinfunction "VCC_8") (pintype "power_in"))
    )
    (net (code "103") (name "Net-(D1-A)") (class "Default")
      (node (ref "D1") (pin "1") (pinfunction "A_1") (pintype "passive"))
      (node (ref "D2") (pin "1") (pinfunction "A_1") (pintype "passive"))
      (node (ref "F1") (pin "1") (pinfunction "1_1") (pintype "passive"))
    )
    (net (code "104") (name "Net-(D3-K)") (class "Default")
      (node (ref "D3") (pin "2") (pinfunction "K_2") (pintype "passive"))
      (node (ref "L1") (pin "1") (pinfunction "1_1") (pintype "passive"))
      (node (ref "U1") (pin "2") (pinfunction "OUT_2") (pintype "output"))
    )
    (net (code "105") (name "Net-(F1-Pad2)") (class "Default")
      (node (ref "F1") (pin "2") (pinfunction "2_2") (pintype "passive"))
      (node (ref "T1") (pin "2") (pinfunction "2_2") (pintype "passive"))
    )
    (net (code "106") (name "Net-(LED0-A)") (class "Default")
      (node (ref "LED0") (pin "1") (pinfunction "A_1") (pintype "passive"))
      (node (ref "R95") (pin "1") (pinfunction "1_1") (pintype "passive"))
    )
    (net (code "107") (name "Net-(U2-R1IN)") (class "Default")
      (node (ref "R1") (pin "2") (pinfunction "2_2") (pintype "passive"))
      (node (ref "U2") (pin "13") (pinfunction "R1IN_13") (pintype "passive"))
    )
    (net (code "108") (name "Net-(U2-T1OUT)") (class "Default")
      (node (ref "R2") (pin "2") (pinfunction "2_2") (pintype "passive"))
      (node (ref "U2") (pin "14") (pinfunction "T1OUT_14") (pintype "passive"))
    )
    (net (code "109") (name "Net-(U3-A)") (class "Default")
      (node (ref "R3") (pin "2") (pinfunction "2_2") (pintype "passive"))
      (node (ref "R4") (pin "1") (pinfunction "1_1") (pintype "passive"))
      (node (ref "R6") (pin "2") (pinfunction "2_2") (pintype "passive"))
      (node (ref "TVS1") (pin "2") (pinfunction "A_2") (pintype "passive"))
      (node (ref "U3") (pin "6") (pinfunction "A_6") (pintype "bidirectional"))
    )
    (net (code "110") (name "Net-(U3-B)") (class "Default")
      (node (ref "R4") (pin "2") (pinfunction "2_2") (pintype "passive"))
      (node (ref "R5") (pin "1") (pinfunction "1_1") (pintype "passive"))
      (node (ref "R7") (pin "2") (pinfunction "2_2") (pintype "passive"))
      (node (ref "TVS1") (pin "1") (pinfunction "A_1") (pintype "passive"))
      (node (ref "U3") (pin "7") (pinfunction "B_7") (pintype "bidirectional"))
    )
    (net (code "111") (name "Net-(U4-VF1-)") (class "Default")
      (node (ref "R39") (pin "2") (pinfunction "2_2") (pintype "passive"))
      (node (ref "U4") (pin "2") (pinfunction "VF1-_2") (pintype "input"))
    )
    (net (code "112") (name "Net-(U4-VF2-)") (class "Default")
      (node (ref "R40") (pin "2") (pinfunction "2_2") (pintype "passive"))
      (node (ref "U4") (pin "3") (pinfunction "VF2-_3") (pintype "input"))
    )
    (net (code "113") (name "Net-(U5-VF1-)") (class "Default")
      (node (ref "R43") (pin "2") (pinfunction "2_2") (pintype "passive"))
      (node (ref "U5") (pin "2") (pinfunction "VF1-_2") (pintype "input"))
    )
    (net (code "114") (name "Net-(U5-VF2-)") (class "Default")
      (node (ref "R44") (pin "2") (pinfunction "2_2") (pintype "passive"))
      (node (ref "U5") (pin "3") (pinfunction "VF2-_3") (pintype "input"))
    )
    (net (code "115") (name "Net-(U6-VF1-)") (class "Default")
      (node (ref "R47") (pin "2") (pinfunction "2_2") (pintype "passive"))
      (node (ref "U6") (pin "2") (pinfunction "VF1-_2") (pintype "input"))
    )
    (net (code "116") (name "Net-(U6-VF2-)") (class "Default")
      (node (ref "R48") (pin "2") (pinfunction "2_2") (pintype "passive"))
      (node (ref "U6") (pin "3") (pinfunction "VF2-_3") (pintype "input"))
    )
    (net (code "117") (name "Net-(U7-VF1-)") (class "Default")
      (node (ref "R51") (pin "2") (pinfunction "2_2") (pintype "passive"))
      (node (ref "U7") (pin "2") (pinfunction "VF1-_2") (pintype "input"))
    )
    (net (code "118") (name "Net-(U7-VF2-)") (class "Default")
      (node (ref "R52") (pin "2") (pinfunction "2_2") (pintype "passive"))
      (node (ref "U7") (pin "3") (pinfunction "VF2-_3") (pintype "input"))
    )
    (net (code "119") (name "Net-(U8-VF1-)") (class "Default")
      (node (ref "R55") (pin "2") (pinfunction "2_2") (pintype "passive"))
      (node (ref "U8") (pin "2") (pinfunction "VF1-_2") (pintype "input"))
    )
    (net (code "120") (name "Net-(U8-VF2-)") (class "Default")
      (node (ref "R56") (pin "2") (pinfunction "2_2") (pintype "passive"))
      (node (ref "U8") (pin "3") (pinfunction "VF2-_3") (pintype "input"))
    )
    (net (code "121") (name "Net-(U9-VF1-)") (class "Default")
      (node (ref "R57") (pin "2") (pinfunction "2_2") (pintype "passive"))
      (node (ref "U9") (pin "2") (pinfunction "VF1-_2") (pintype "input"))
    )
    (net (code "122") (name "Net-(U9-VF2-)") (class "Default")
      (node (ref "R58") (pin "2") (pinfunction "2_2") (pintype "passive"))
      (node (ref "U9") (pin "3") (pinfunction "VF2-_3") (pintype "input"))
    )
    (net (code "123") (name "Net-(U10-VF1-)") (class "Default")
      (node (ref "R59") (pin "2") (pinfunction "2_2") (pintype "passive"))
      (node (ref "U10") (pin "2") (pinfunction "VF1-_2") (pintype "input"))
    )
    (net (code "124") (name "Net-(U10-VF2-)") (class "Default")
      (node (ref "R60") (pin "2") (pinfunction "2_2") (pintype "passive"))
      (node (ref "U10") (pin "3") (pinfunction "VF2-_3") (pintype "input"))
    )
    (net (code "125") (name "Net-(U11-VF1-)") (class "Default")
      (node (ref "R61") (pin "2") (pinfunction "2_2") (pintype "passive"))
      (node (ref "U11") (pin "2") (pinfunction "VF1-_2") (pintype "input"))
    )
    (net (code "126") (name "Net-(U11-VF2-)") (class "Default")
      (node (ref "R62") (pin "2") (pinfunction "2_2") (pintype "passive"))
      (node (ref "U11") (pin "3") (pinfunction "VF2-_3") (pintype "input"))
    )
    (net (code "127") (name "Net-(U13-1Y)") (class "Default")
      (node (ref "R87") (pin "1") (pinfunction "1_1") (pintype "passive"))
      (node (ref "U13") (pin "2") (pinfunction "1Y_2") (pintype "output"))
    )
    (net (code "128") (name "Net-(U13-2Y)") (class "Default")
      (node (ref "R88") (pin "1") (pinfunction "1_1") (pintype "passive"))
      (node (ref "U13") (pin "4") (pinfunction "2Y_4") (pintype "output"))
    )
    (net (code "129") (name "Net-(U13-5Y)") (class "Default")
      (node (ref "R89") (pin "1") (pinfunction "1_1") (pintype "passive"))
      (node (ref "U13") (pin "10") (pinfunction "5Y_10") (pintype "output"))
    )
    (net (code "130") (name "Net-(U13-6Y)") (class "Default")
      (node (ref "R90") (pin "1") (pinfunction "1_1") (pintype "passive"))
      (node (ref "U13") (pin "12") (pinfunction "6Y_12") (pintype "output"))
    )
    (net (code "131") (name "VDD_5V") (class "Default")
      (node (ref "C11") (pin "2") (pinfunction "P_2") (pintype "passive"))
      (node (ref "C12") (pin "1") (pinfunction "+_1") (pintype "passive"))
      (node (ref "C17") (pin "2") (pinfunction "-_2") (pintype "passive"))
      (node (ref "C18") (pin "2") (pinfunction "-_2") (pintype "passive"))
      (node (ref "C19") (pin "2") (pinfunction "-_2") (pintype "passive"))
      (node (ref "C20") (pin "2") (pinfunction "-_2") (pintype "passive"))
      (node (ref "C21") (pin "2") (pinfunction "-_2") (pintype "passive"))
      (node (ref "C22") (pin "2") (pinfunction "-_2") (pintype "passive"))
      (node (ref "C23") (pin "2") (pinfunction "-_2") (pintype "passive"))
      (node (ref "C24") (pin "2") (pinfunction "-_2") (pintype "passive"))
      (node (ref "C3") (pin "2") (pinfunction "P_2") (pintype "passive"))
      (node (ref "C33") (pin "2") (pinfunction "-_2") (pintype "passive"))
      (node (ref "C34") (pin "2") (pinfunction "-_2") (pintype "passive"))
      (node (ref "C4") (pin "2") (pinfunction "P_2") (pintype "passive"))
      (node (ref "C5") (pin "1") (pinfunction "+_1") (pintype "passive"))
      (node (ref "L1") (pin "2") (pinfunction "2_2") (pintype "passive"))
      (node (ref "R24") (pin "1") (pinfunction "1_1") (pintype "passive"))
      (node (ref "R26") (pin "1") (pinfunction "1_1") (pintype "passive"))
      (node (ref "R28") (pin "1") (pinfunction "1_1") (pintype "passive"))
      (node (ref "R30") (pin "1") (pinfunction "1_1") (pintype "passive"))
      (node (ref "R32") (pin "1") (pinfunction "1_1") (pintype "passive"))
      (node (ref "R34") (pin "1") (pinfunction "1_1") (pintype "passive"))
      (node (ref "R36") (pin "1") (pinfunction "1_1") (pintype "passive"))
      (node (ref "R38") (pin "1") (pinfunction "1_1") (pintype "passive"))
      (node (ref "R76") (pin "1") (pinfunction "1_1") (pintype "passive"))
      (node (ref "R77") (pin "1") (pinfunction "1_1") (pintype "passive"))
      (node (ref "R78") (pin "1") (pinfunction "1_1") (pintype "passive"))
      (node (ref "R79") (pin "1") (pinfunction "1_1") (pintype "passive"))
      (node (ref "R81") (pin "1") (pinfunction "1_1") (pintype "passive"))
      (node (ref "R82") (pin "1") (pinfunction "1_1") (pintype "passive"))
      (node (ref "R84") (pin "1") (pinfunction "1_1") (pintype "passive"))
      (node (ref "R85") (pin "1") (pinfunction "1_1") (pintype "passive"))
      (node (ref "U1") (pin "4") (pinfunction "FB_4") (pintype "input"))
      (node (ref "U10") (pin "8") (pinfunction "VCC_8") (pintype "power_in"))
      (node (ref "U11") (pin "8") (pinfunction "VCC_8") (pintype "power_in"))
      (node (ref "U12") (pin "12") (pinfunction "3,4EN_12") (pintype "bidirectional"))
      (node (ref "U12") (pin "16") (pinfunction "VCC_16") (pintype "power_in"))
      (node (ref "U12") (pin "4") (pinfunction "1,2EN_4") (pintype "bidirectional"))
      (node (ref "U13") (pin "14") (pinfunction "VCC_14") (pintype "power_in"))
      (node (ref "U4") (pin "8") (pinfunction "VCC_8") (pintype "power_in"))
      (node (ref "U5") (pin "8") (pinfunction "VCC_8") (pintype "power_in"))
      (node (ref "U6") (pin "8") (pinfunction "VCC_8") (pintype "power_in"))
      (node (ref "U7") (pin "8") (pinfunction "VCC_8") (pintype "power_in"))
      (node (ref "U8") (pin "8") (pinfunction "VCC_8") (pintype "power_in"))
      (node (ref "U9") (pin "8") (pinfunction "VCC_8") (pintype "power_in"))
      (node (ref "UP1") (pin "3") (pinfunction "IN_3") (pintype "power_in"))
    )
    (net (code "132") (name "unconnected-(P2-Pad9)") (class "Default")
      (node (ref "P2") (pin "9") (pinfunction "9_9") (pintype "passive"))
    )
    (net (code "133") (name "unconnected-(U2-R2IN-Pad8)") (class "Default")
      (node (ref "U2") (pin "8") (pinfunction "R2IN_8") (pintype "passive"))
    )
    (net (code "134") (name "unconnected-(U2-R2OUT-Pad9)") (class "Default")
      (node (ref "U2") (pin "9") (pinfunction "R2OUT_9") (pintype "passive"))
    )
    (net (code "135") (name "unconnected-(U2-T2IN-Pad10)") (class "Default")
      (node (ref "U2") (pin "10") (pinfunction "T2IN_10") (pintype "passive"))
    )
    (net (code "136") (name "unconnected-(U2-T2OUT-Pad7)") (class "Default")
      (node (ref "U2") (pin "7") (pinfunction "T2OUT_7") (pintype "passive"))
    )
    (net (code "137") (name "unconnected-(U13-3A-Pad5)") (class "Default")
      (node (ref "U13") (pin "5") (pinfunction "3A_5") (pintype "input"))
    )
    (net (code "138") (name "unconnected-(U13-3Y-Pad6)") (class "Default")
      (node (ref "U13") (pin "6") (pinfunction "3Y_6") (pintype "output"))
    )
    (net (code "139") (name "unconnected-(U13-4A-Pad9)") (class "Default")
      (node (ref "U13") (pin "9") (pinfunction "4A_9") (pintype "input"))
    )
    (net (code "140") (name "unconnected-(U13-4Y-Pad8)") (class "Default")
      (node (ref "U13") (pin "8") (pinfunction "4Y_8") (pintype "output"))
    )
  )
)
